# CntrlBoardV2_0.net
KiCad netlist of a schematic drawn in EAGLE
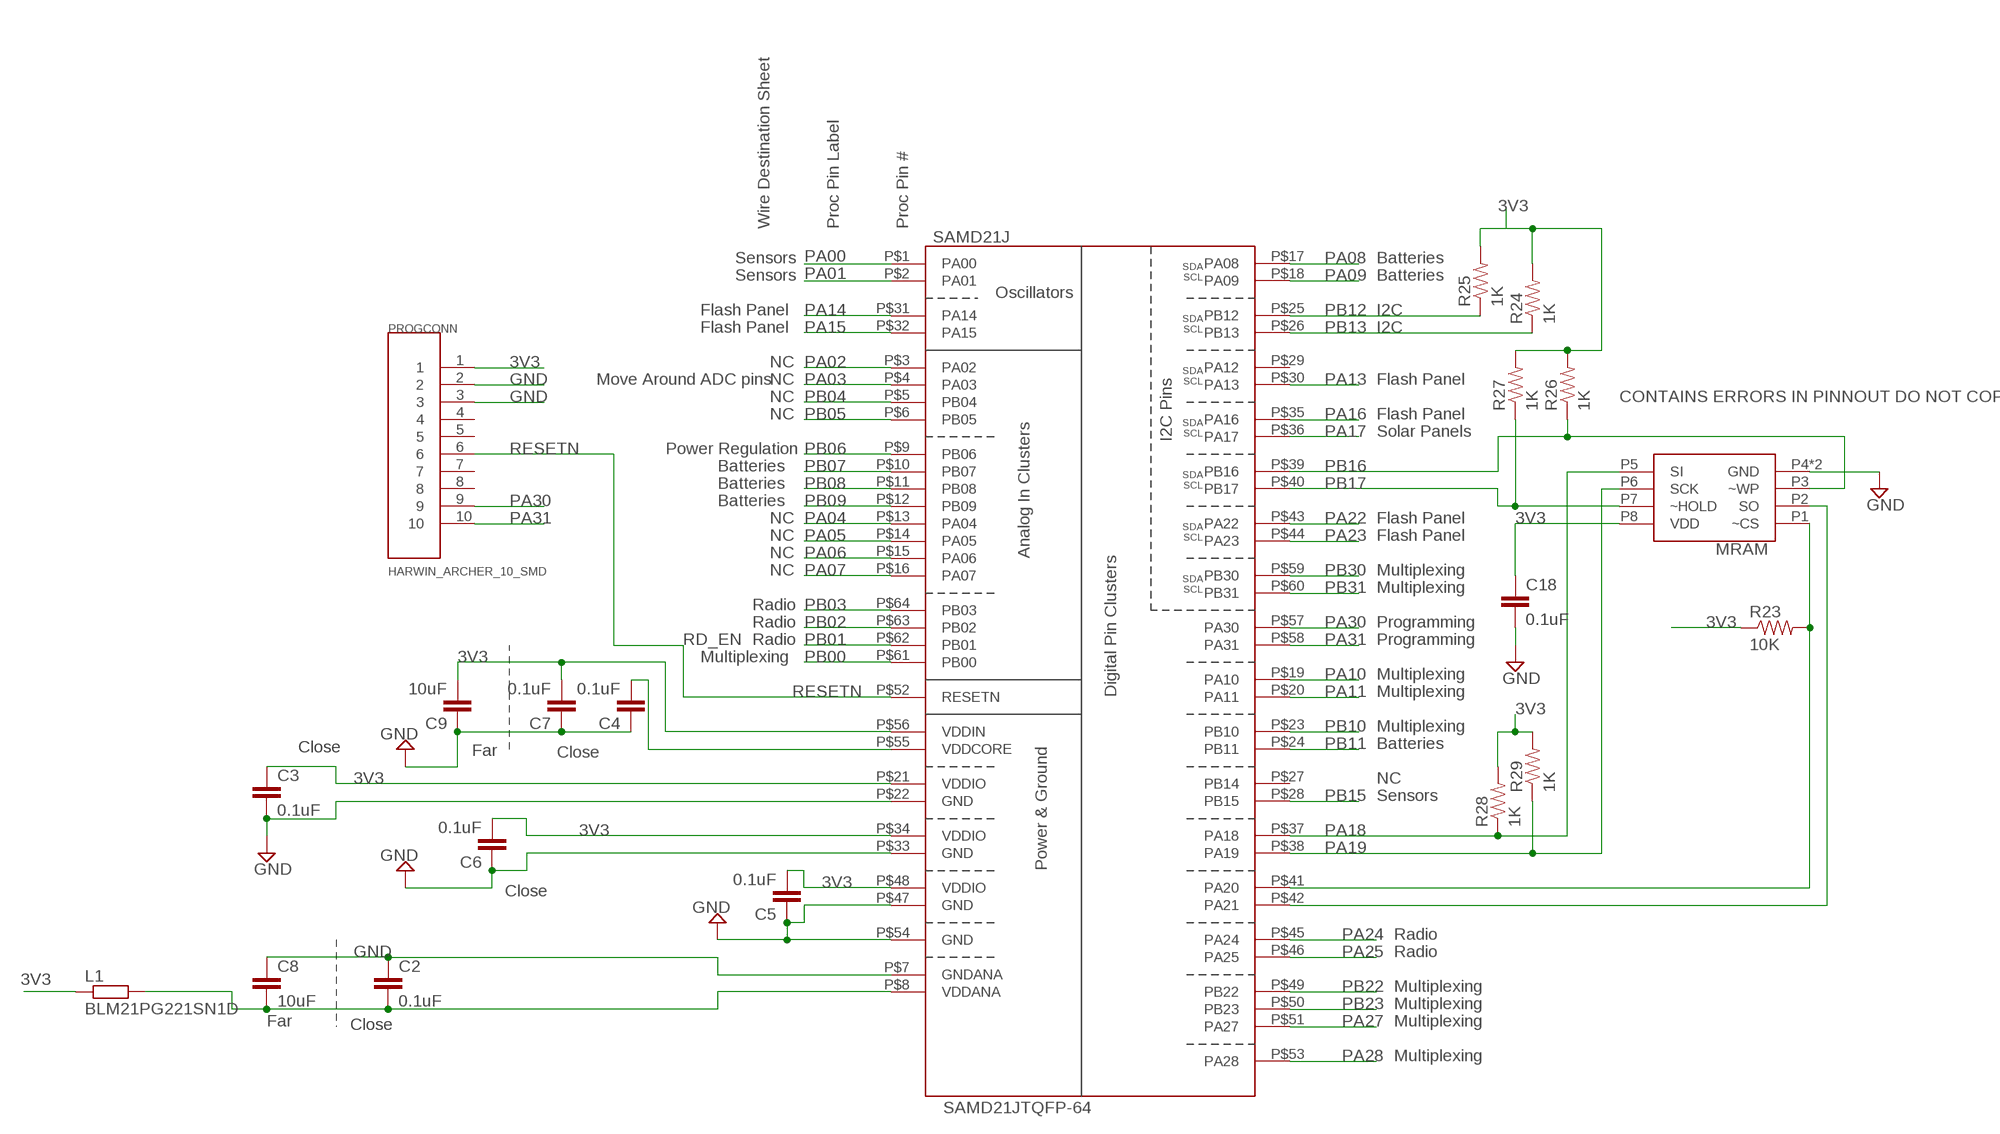
[diagram p0: schematic, sheet 1]
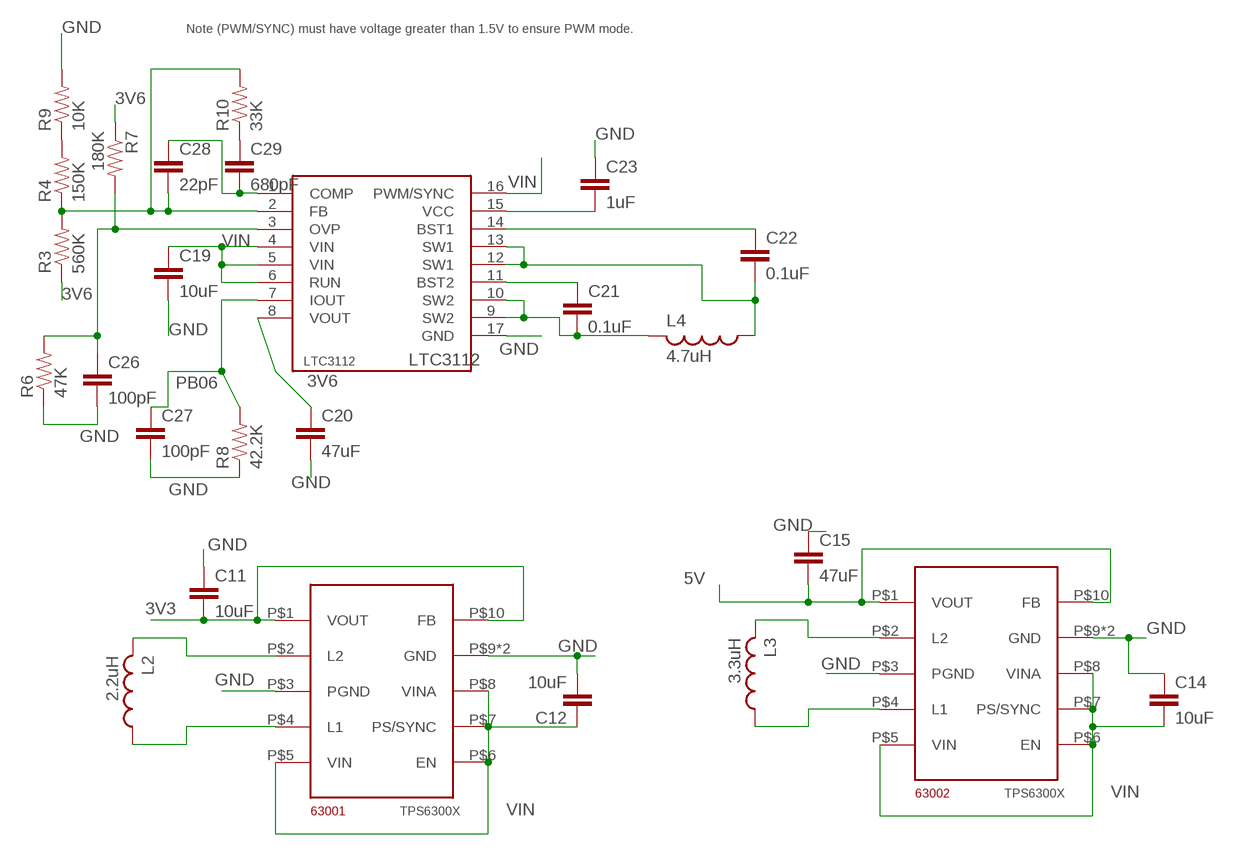
[diagram p1: schematic, sheet 2]
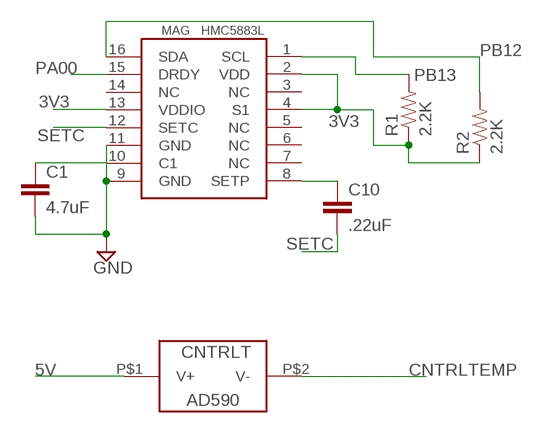
[diagram p2: schematic, sheet 3]
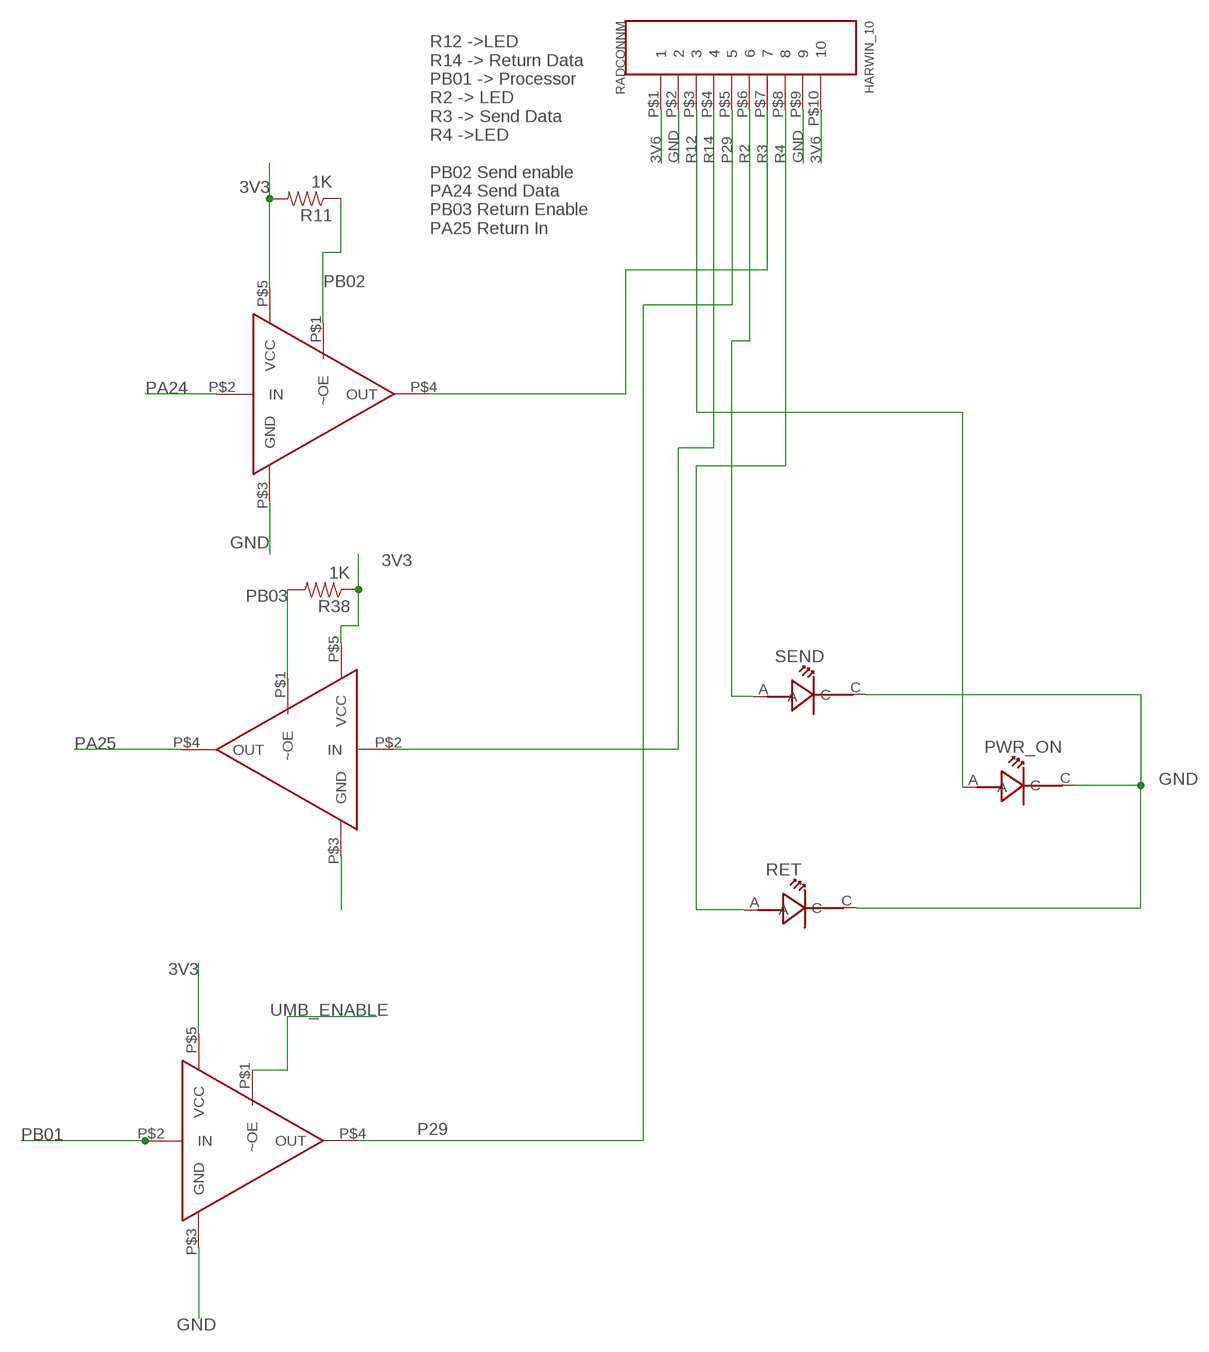
[diagram p3: schematic, sheet 4]
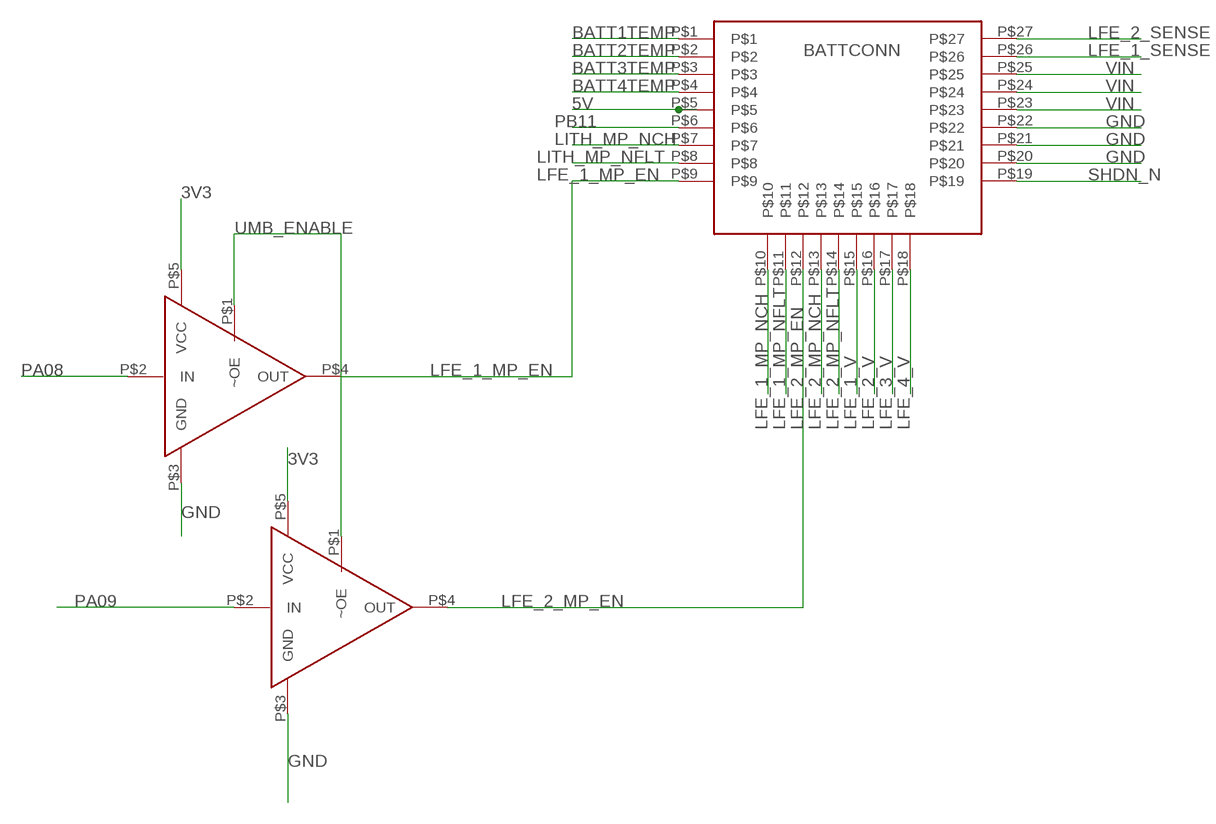
[diagram p4: schematic, sheet 5]
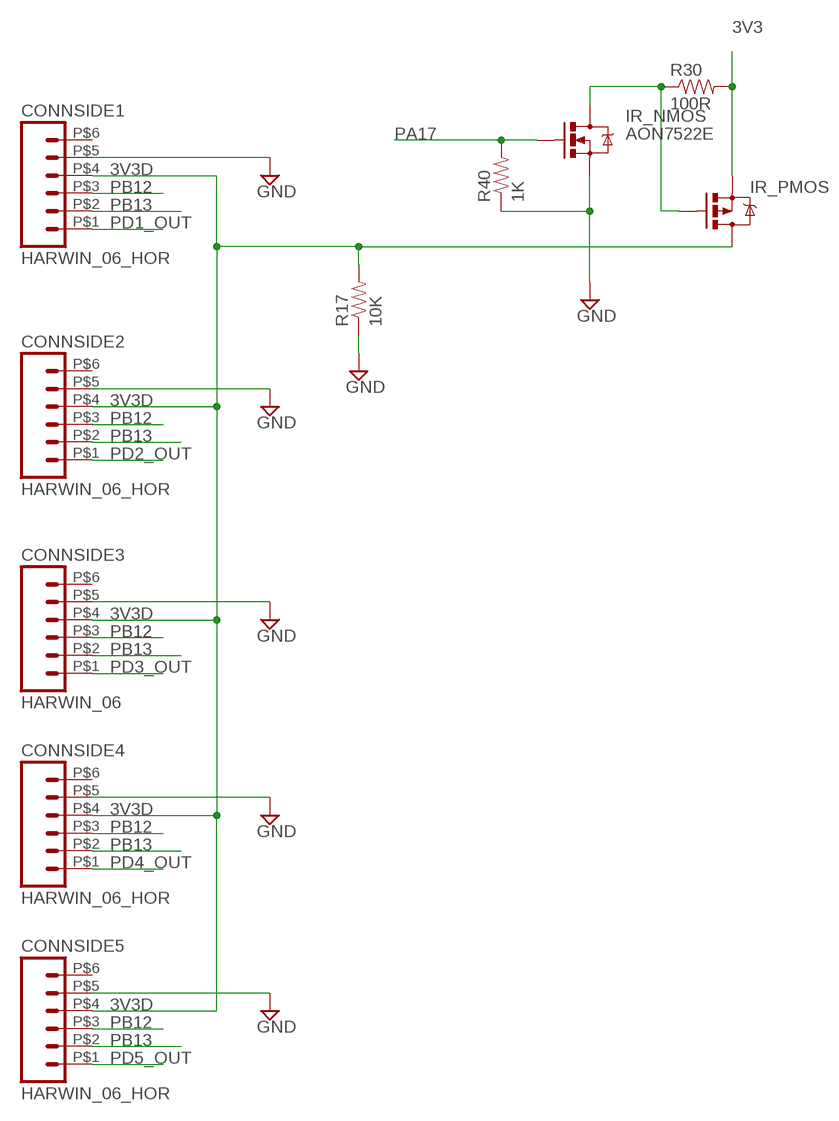
[diagram p5: schematic, sheet 6]
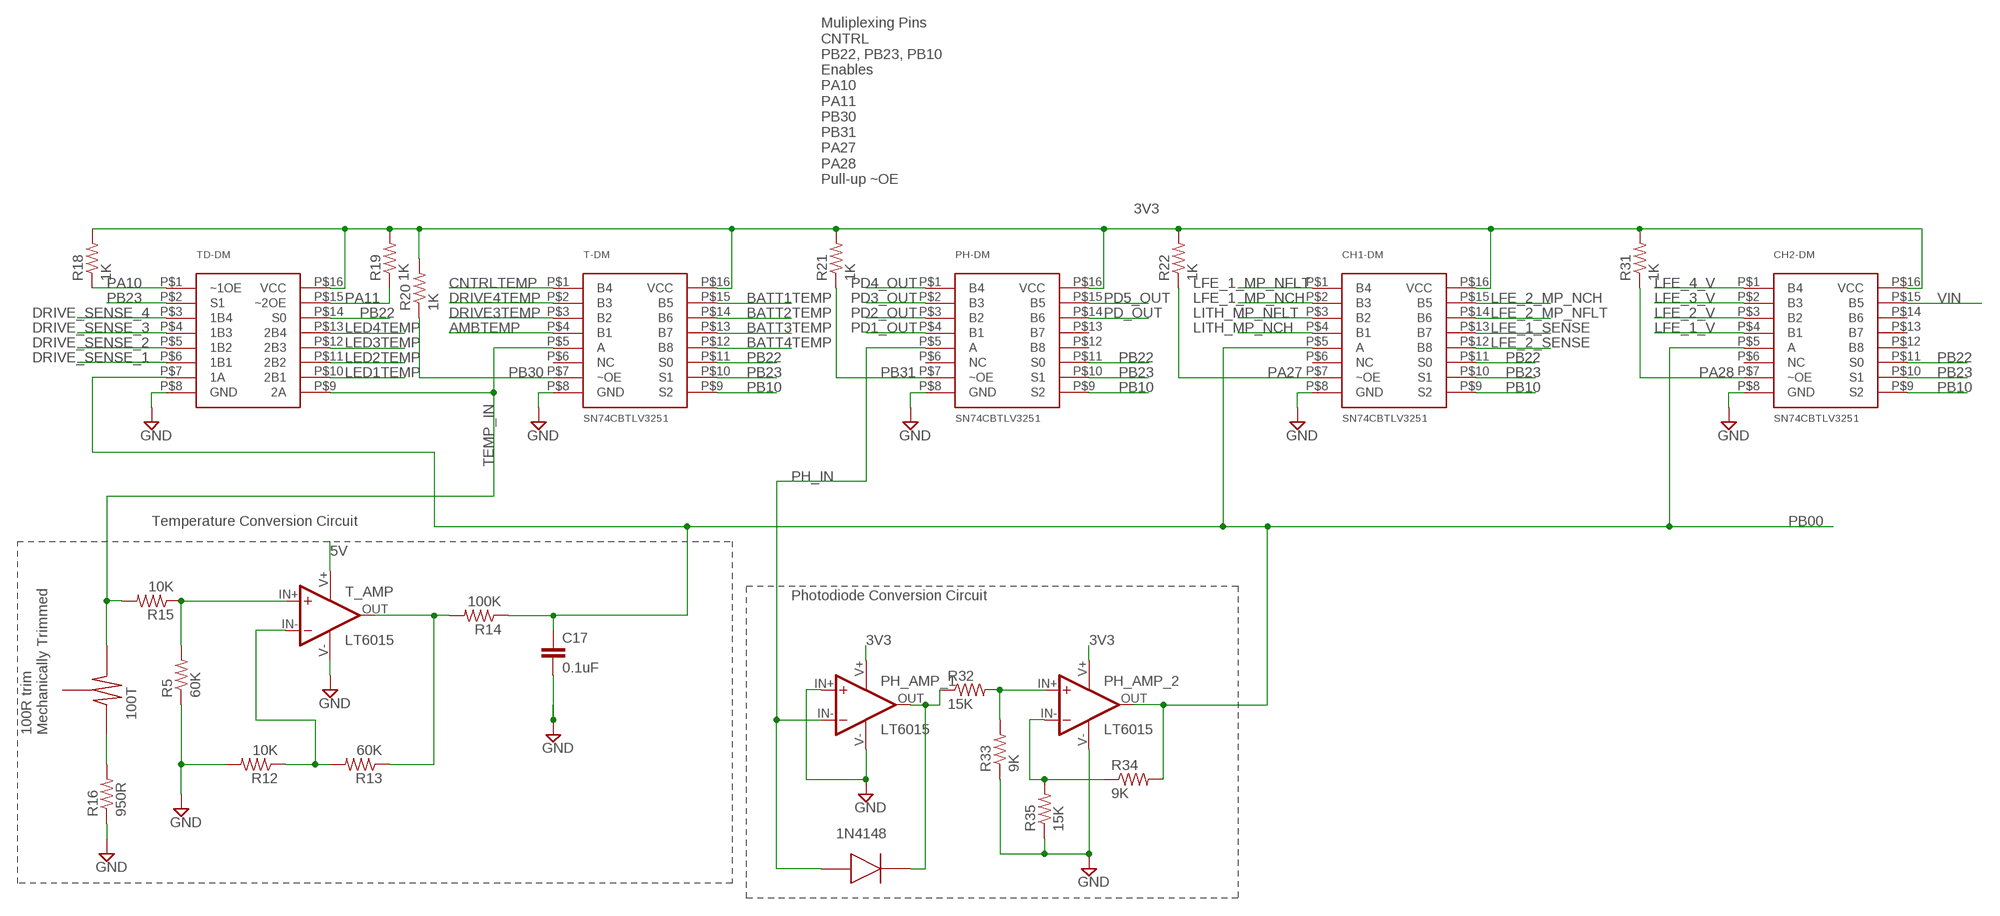
[diagram p6: schematic, sheet 7]
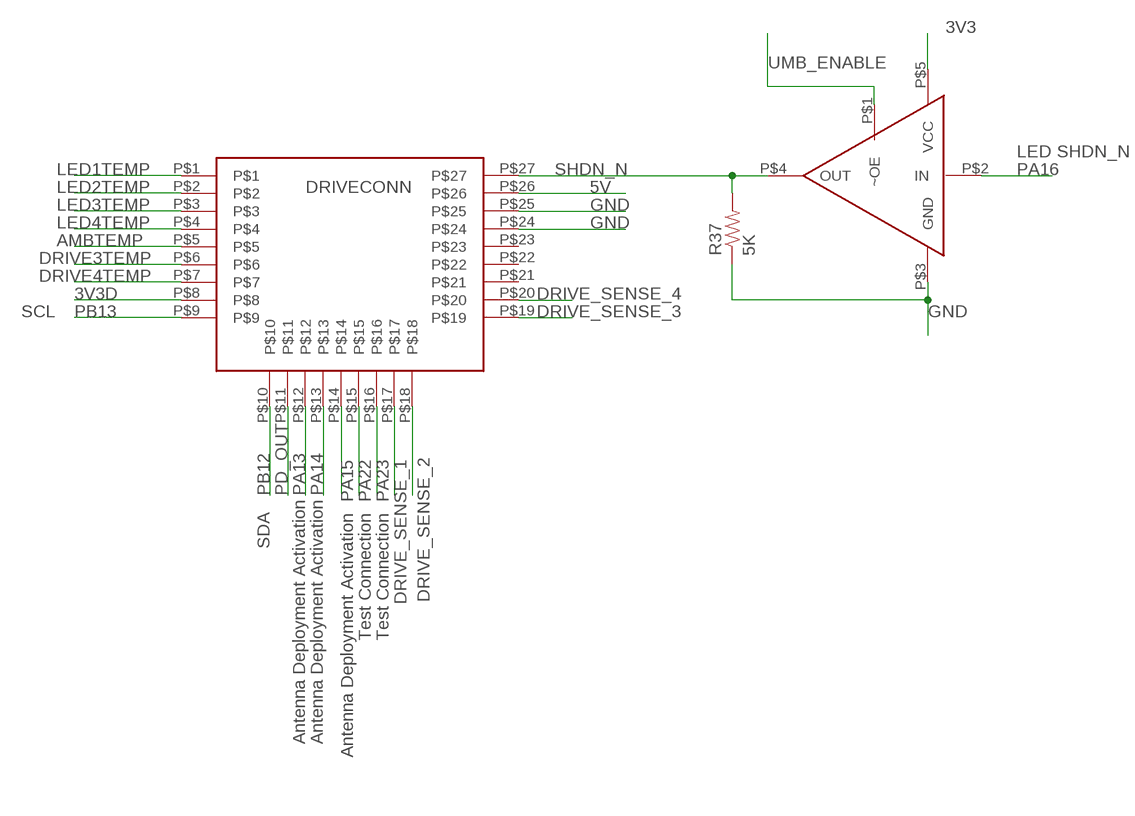
[diagram p7: schematic, sheet 8]
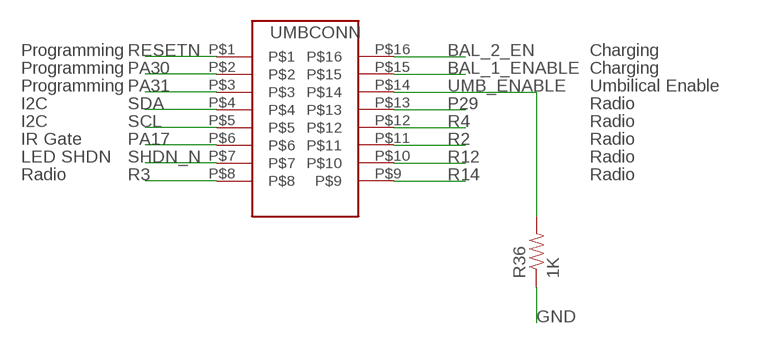
[diagram p8: schematic, sheet 9]

(export (version "E")
  (design (tool "Eeschema 10.0.6"))
  (components
    (comp (ref "R36")
      (value "1K")
      (footprint "eagle-import:0805")
      (libsource (lib "eagle-import") (part "RESISTOR"))
    )
    (comp (ref "UMBCONN")
      (value "HARWIN_16")
      (footprint "eagle-import:HARWIN_DATAMATE_16")
      (libsource (lib "eagle-import") (part "HARWIN_16"))
    )
    (comp (ref "1N4148")
      (value "1N4148WS")
      (footprint "eagle-import:SOD-323F")
      (libsource (lib "eagle-import") (part "1N4148WS"))
    )
    (comp (ref "100T")
      (value "TRIMPOT-TC33")
      (footprint "eagle-import:TC33X-2")
      (libsource (lib "eagle-import") (part "TRIMPOT-TC33"))
    )
    (comp (ref "C17")
      (value "0.1uF")
      (footprint "eagle-import:0805")
      (libsource (lib "eagle-import") (part "CAP0805"))
    )
    (comp (ref "CH1-DM")
      (value "SN74CBTLV3251")
      (footprint "eagle-import:TSSOP-16")
      (libsource (lib "eagle-import") (part "SN74CBTLV3251"))
    )
    (comp (ref "CH2-DM")
      (value "SN74CBTLV3251")
      (footprint "eagle-import:TSSOP-16")
      (libsource (lib "eagle-import") (part "SN74CBTLV3251"))
    )
    (comp (ref "PH-DM")
      (value "SN74CBTLV3251")
      (footprint "eagle-import:TSSOP-16")
      (libsource (lib "eagle-import") (part "SN74CBTLV3251"))
    )
    (comp (ref "PH_AMP_1")
      (value "LT6015")
      (footprint "eagle-import:SOT23-5")
      (libsource (lib "eagle-import") (part "LT6015"))
    )
    (comp (ref "PH_AMP_2")
      (value "LT6015")
      (footprint "eagle-import:SOT23-5")
      (libsource (lib "eagle-import") (part "LT6015"))
    )
    (comp (ref "R5")
      (value "60K")
      (footprint "eagle-import:0805")
      (libsource (lib "eagle-import") (part "RESISTOR"))
    )
    (comp (ref "R12")
      (value "10K")
      (footprint "eagle-import:0805")
      (libsource (lib "eagle-import") (part "RESISTOR"))
    )
    (comp (ref "R13")
      (value "60K")
      (footprint "eagle-import:0805")
      (libsource (lib "eagle-import") (part "RESISTOR"))
    )
    (comp (ref "R14")
      (value "100K")
      (footprint "eagle-import:0805")
      (libsource (lib "eagle-import") (part "RESISTOR"))
    )
    (comp (ref "R15")
      (value "10K")
      (footprint "eagle-import:0805")
      (libsource (lib "eagle-import") (part "RESISTOR"))
    )
    (comp (ref "R16")
      (value "950R")
      (footprint "eagle-import:0805")
      (libsource (lib "eagle-import") (part "RESISTOR"))
    )
    (comp (ref "R18")
      (value "1K")
      (footprint "eagle-import:0805")
      (libsource (lib "eagle-import") (part "RESISTOR"))
    )
    (comp (ref "R19")
      (value "1K")
      (footprint "eagle-import:0805")
      (libsource (lib "eagle-import") (part "RESISTOR"))
    )
    (comp (ref "R20")
      (value "1K")
      (footprint "eagle-import:0805")
      (libsource (lib "eagle-import") (part "RESISTOR"))
    )
    (comp (ref "R21")
      (value "1K")
      (footprint "eagle-import:0805")
      (libsource (lib "eagle-import") (part "RESISTOR"))
    )
    (comp (ref "R22")
      (value "1K")
      (footprint "eagle-import:0805")
      (libsource (lib "eagle-import") (part "RESISTOR"))
    )
    (comp (ref "R31")
      (value "1K")
      (footprint "eagle-import:0805")
      (libsource (lib "eagle-import") (part "RESISTOR"))
    )
    (comp (ref "R32")
      (value "15K")
      (footprint "eagle-import:0805")
      (libsource (lib "eagle-import") (part "RESISTOR"))
    )
    (comp (ref "R33")
      (value "9K")
      (footprint "eagle-import:0805")
      (libsource (lib "eagle-import") (part "RESISTOR"))
    )
    (comp (ref "R34")
      (value "9K")
      (footprint "eagle-import:0805")
      (libsource (lib "eagle-import") (part "RESISTOR"))
    )
    (comp (ref "R35")
      (value "15K")
      (footprint "eagle-import:0805")
      (libsource (lib "eagle-import") (part "RESISTOR"))
    )
    (comp (ref "T-DM")
      (value "SN74CBTLV3251")
      (footprint "eagle-import:TSSOP-16")
      (libsource (lib "eagle-import") (part "SN74CBTLV3251"))
    )
    (comp (ref "TD-DM")
      (value "SN74CBTLV3253")
      (footprint "eagle-import:TSSOP-16")
      (libsource (lib "eagle-import") (part "SN74CBTLV3253"))
    )
    (comp (ref "T_AMP")
      (value "LT6015")
      (footprint "eagle-import:SOT23-5")
      (libsource (lib "eagle-import") (part "LT6015"))
    )
    (comp (ref "C2")
      (value "0.1uF")
      (footprint "eagle-import:0805")
      (fields (field (name "MPN") "0603YC104JAT2A"))
      (libsource (lib "eagle-import") (part "CAP0805"))
    )
    (comp (ref "C3")
      (value "0.1uF")
      (footprint "eagle-import:0805")
      (fields (field (name "MPN") "0603YC104JAT2A"))
      (libsource (lib "eagle-import") (part "CAP0805"))
    )
    (comp (ref "C4")
      (value "0.1uF")
      (footprint "eagle-import:0805")
      (fields (field (name "MPN") "0603YC104JAT2A"))
      (libsource (lib "eagle-import") (part "CAP0805"))
    )
    (comp (ref "C5")
      (value "0.1uF")
      (footprint "eagle-import:0805")
      (fields (field (name "MPN") "0603YC104JAT2A"))
      (libsource (lib "eagle-import") (part "CAP0805"))
    )
    (comp (ref "C6")
      (value "0.1uF")
      (footprint "eagle-import:0805")
      (fields (field (name "MPN") "0603YC104JAT2A"))
      (libsource (lib "eagle-import") (part "CAP0805"))
    )
    (comp (ref "C7")
      (value "0.1uF")
      (footprint "eagle-import:0805")
      (fields (field (name "MPN") "0603YC104JAT2A"))
      (libsource (lib "eagle-import") (part "CAP0805"))
    )
    (comp (ref "C8")
      (value "10uF")
      (footprint "eagle-import:0805")
      (fields (field (name "MF") "AVX CORPORATION") (field (name "MPN") "08056D106KAT2A"))
      (libsource (lib "eagle-import") (part "CAP0805"))
    )
    (comp (ref "C9")
      (value "10uF")
      (footprint "eagle-import:0805")
      (fields (field (name "MF") "AVX CORPORATION") (field (name "MPN") "08056D106KAT2A"))
      (libsource (lib "eagle-import") (part "CAP0805"))
    )
    (comp (ref "C18")
      (value "0.1uF")
      (footprint "eagle-import:0805")
      (fields (field (name "MPN") "0603YC104JAT2A"))
      (libsource (lib "eagle-import") (part "CAP0805"))
    )
    (comp (ref "L1")
      (value "BLM21PG221SN1D")
      (footprint "eagle-import:R0805")
      (libsource (lib "eagle-import") (part "R-EU_R0805"))
    )
    (comp (ref "MRAM")
      (value "MR25H10CDC")
      (footprint "eagle-import:8PXMO-229")
      (libsource (lib "eagle-import") (part "MR25H10CDC"))
    )
    (comp (ref "PROGCONN")
      (value "HARWIN_ARCHER_10_SMD")
      (footprint "eagle-import:HARWIN_ARCHER_10_SMD")
      (libsource (lib "eagle-import") (part "HARWIN_ARCHER_10_SMD"))
    )
    (comp (ref "R23")
      (value "10K")
      (footprint "eagle-import:0805")
      (libsource (lib "eagle-import") (part "RESISTOR"))
    )
    (comp (ref "R24")
      (value "1K")
      (footprint "eagle-import:0805")
      (libsource (lib "eagle-import") (part "RESISTOR"))
    )
    (comp (ref "R25")
      (value "1K")
      (footprint "eagle-import:0805")
      (libsource (lib "eagle-import") (part "RESISTOR"))
    )
    (comp (ref "R26")
      (value "1K")
      (footprint "eagle-import:0805")
      (libsource (lib "eagle-import") (part "RESISTOR"))
    )
    (comp (ref "R27")
      (value "1K")
      (footprint "eagle-import:0805")
      (libsource (lib "eagle-import") (part "RESISTOR"))
    )
    (comp (ref "R28")
      (value "1K")
      (footprint "eagle-import:0805")
      (libsource (lib "eagle-import") (part "RESISTOR"))
    )
    (comp (ref "R29")
      (value "1K")
      (footprint "eagle-import:0805")
      (libsource (lib "eagle-import") (part "RESISTOR"))
    )
    (comp (ref "SAMD21J")
      (value "SAMD21JTQFP-64")
      (footprint "eagle-import:TQFP-64")
      (libsource (lib "eagle-import") (part "SAMD21JTQFP-64"))
    )
    (comp (ref "BAL_1_BUF")
      (value "SN74LVC1G125")
      (footprint "eagle-import:SC70")
      (libsource (lib "eagle-import") (part "SN74LVC1G125"))
    )
    (comp (ref "BAL_2_BUF")
      (value "SN74LVC1G125")
      (footprint "eagle-import:SC70")
      (libsource (lib "eagle-import") (part "SN74LVC1G125"))
    )
    (comp (ref "BATTCONN")
      (value "HARWIN_27")
      (footprint "eagle-import:HARWIN_DATAMATE_27")
      (libsource (lib "eagle-import") (part "HARWIN_27"))
    )
    (comp (ref "DRIVECONN")
      (value "HARWIN_27_HOR")
      (footprint "eagle-import:HARWIN_DATAMATE_27_HOR")
      (libsource (lib "eagle-import") (part "HARWIN_27_HOR"))
    )
    (comp (ref "LED_EN_BUF")
      (value "SN74LVC1G125")
      (footprint "eagle-import:SC70")
      (libsource (lib "eagle-import") (part "SN74LVC1G125"))
    )
    (comp (ref "R37")
      (value "5K")
      (footprint "eagle-import:0805")
      (libsource (lib "eagle-import") (part "RESISTOR"))
    )
    (comp (ref "C1")
      (value "4.7uF")
      (footprint "eagle-import:0805")
      (fields (field (name "MF") "AVX CORPORATION") (field (name "MPN") "08056D475KAT2A"))
      (libsource (lib "eagle-import") (part "CAP0805"))
    )
    (comp (ref "C10")
      (value ".22uF")
      (footprint "eagle-import:0805")
      (fields (field (name "MF") "AVX CORPORATION") (field (name "MPN") "08053C224KAT2A"))
      (libsource (lib "eagle-import") (part "CAP0805"))
    )
    (comp (ref "CNTRLT")
      (value "AD590-TH")
      (footprint "eagle-import:AD590TH")
      (libsource (lib "eagle-import") (part "AD590-TH"))
    )
    (comp (ref "MAG")
      (value "HMC5883L")
      (footprint "eagle-import:HMC5883L")
      (fields (field (name "MPN") "HMC5883L-TR"))
      (libsource (lib "eagle-import") (part "HMC5883L"))
    )
    (comp (ref "R1")
      (value "2.2K")
      (footprint "eagle-import:0805")
      (fields (field (name "MPN") "SR1-0805-222"))
      (libsource (lib "eagle-import") (part "RESISTOR"))
    )
    (comp (ref "R2")
      (value "2.2K")
      (footprint "eagle-import:0805")
      (fields (field (name "MPN") "SR1-0805-222"))
      (libsource (lib "eagle-import") (part "RESISTOR"))
    )
    (comp (ref "PWR_ON")
      (value "LT-T673-Q1R2-25-Z")
      (footprint "eagle-import:PLCC-2")
      (libsource (lib "eagle-import") (part "LT-T673-Q1R2-25-Z"))
    )
    (comp (ref "R11")
      (value "1K")
      (footprint "eagle-import:0805")
      (libsource (lib "eagle-import") (part "RESISTOR"))
    )
    (comp (ref "R38")
      (value "1K")
      (footprint "eagle-import:0805")
      (libsource (lib "eagle-import") (part "RESISTOR"))
    )
    (comp (ref "RADCONNM")
      (value "HARWIN_10")
      (footprint "eagle-import:HARWIN_DATAMATE_10")
      (libsource (lib "eagle-import") (part "HARWIN_10"))
    )
    (comp (ref "RAD_SHDN_BUF")
      (value "SN74LVC1G125")
      (footprint "eagle-import:SC70")
      (libsource (lib "eagle-import") (part "SN74LVC1G125"))
    )
    (comp (ref "RET")
      (value "LT-T673-Q1R2-25-Z")
      (footprint "eagle-import:PLCC-2")
      (libsource (lib "eagle-import") (part "LT-T673-Q1R2-25-Z"))
    )
    (comp (ref "RX_BUF")
      (value "SN74LVC1G125")
      (footprint "eagle-import:SC70")
      (libsource (lib "eagle-import") (part "SN74LVC1G125"))
    )
    (comp (ref "SEND")
      (value "LT-T673-Q1R2-25-Z")
      (footprint "eagle-import:PLCC-2")
      (libsource (lib "eagle-import") (part "LT-T673-Q1R2-25-Z"))
    )
    (comp (ref "TX_BUF")
      (value "SN74LVC1G125")
      (footprint "eagle-import:SC70")
      (libsource (lib "eagle-import") (part "SN74LVC1G125"))
    )
    (comp (ref "CONNSIDE1")
      (value "HARWIN_06_HOR")
      (footprint "eagle-import:HARWIN_DATAMATE_6_HOR")
      (libsource (lib "eagle-import") (part "HARWIN_06_HOR"))
    )
    (comp (ref "CONNSIDE2")
      (value "HARWIN_06_HOR")
      (footprint "eagle-import:HARWIN_DATAMATE_6_HOR")
      (libsource (lib "eagle-import") (part "HARWIN_06_HOR"))
    )
    (comp (ref "CONNSIDE3")
      (value "HARWIN_06")
      (footprint "eagle-import:HARWIN_DATAMATE_6")
      (libsource (lib "eagle-import") (part "HARWIN_06"))
    )
    (comp (ref "CONNSIDE4")
      (value "HARWIN_06_HOR")
      (footprint "eagle-import:HARWIN_DATAMATE_6_HOR")
      (libsource (lib "eagle-import") (part "HARWIN_06_HOR"))
    )
    (comp (ref "CONNSIDE5")
      (value "HARWIN_06_HOR")
      (footprint "eagle-import:HARWIN_DATAMATE_6_HOR")
      (libsource (lib "eagle-import") (part "HARWIN_06_HOR"))
    )
    (comp (ref "IR_NMOS")
      (value "AON7522E")
      (footprint "eagle-import:DFN3")
      (libsource (lib "eagle-import") (part "AON7522E"))
    )
    (comp (ref "IR_PMOS")
      (value "POWERPMOS")
      (footprint "eagle-import:SO08")
      (libsource (lib "eagle-import") (part "POWERPMOS"))
    )
    (comp (ref "R17")
      (value "10K")
      (footprint "eagle-import:0805")
      (libsource (lib "eagle-import") (part "RESISTOR"))
    )
    (comp (ref "R30")
      (value "100R")
      (footprint "eagle-import:0805")
      (libsource (lib "eagle-import") (part "RESISTOR"))
    )
    (comp (ref "R40")
      (value "1K")
      (footprint "eagle-import:0805")
      (libsource (lib "eagle-import") (part "RESISTOR"))
    )
    (comp (ref "63001")
      (value "TPS6300X")
      (footprint "eagle-import:QFN10_POWERPAD")
      (libsource (lib "eagle-import") (part "TPS6300X"))
    )
    (comp (ref "63002")
      (value "TPS6300X")
      (footprint "eagle-import:QFN10_POWERPAD")
      (libsource (lib "eagle-import") (part "TPS6300X"))
    )
    (comp (ref "C11")
      (value "10uF")
      (footprint "eagle-import:0603-CAP")
      (libsource (lib "eagle-import") (part "CAP0603-CAP"))
    )
    (comp (ref "C12")
      (value "10uF")
      (footprint "eagle-import:0603-CAP")
      (libsource (lib "eagle-import") (part "CAP0603-CAP"))
    )
    (comp (ref "C14")
      (value "10uF")
      (footprint "eagle-import:0603-CAP")
      (fields (field (name "MPN") "C1608X5R1A225K080AC"))
      (libsource (lib "eagle-import") (part "CAP0603-CAP"))
    )
    (comp (ref "C15")
      (value "47uF")
      (footprint "eagle-import:0603-CAP")
      (fields (field (name "MPN") "EMK107B7474KA-T"))
      (libsource (lib "eagle-import") (part "CAP0603-CAP"))
    )
    (comp (ref "C19")
      (value "10uF")
      (footprint "eagle-import:0603-CAP")
      (libsource (lib "eagle-import") (part "CAP0603-CAP"))
    )
    (comp (ref "C20")
      (value "47uF")
      (footprint "eagle-import:0805")
      (fields (field (name "MPN") "EMK107B7474KA-T"))
      (libsource (lib "eagle-import") (part "CAP0805"))
    )
    (comp (ref "C21")
      (value "0.1uF")
      (footprint "eagle-import:0603-CAP")
      (fields (field (name "MPN") "0603YC104JAT2A"))
      (libsource (lib "eagle-import") (part "CAP0603-CAP"))
    )
    (comp (ref "C22")
      (value "0.1uF")
      (footprint "eagle-import:0603-CAP")
      (fields (field (name "MPN") "0603YC104JAT2A"))
      (libsource (lib "eagle-import") (part "CAP0603-CAP"))
    )
    (comp (ref "C23")
      (value "1uF")
      (footprint "eagle-import:0603-CAP")
      (libsource (lib "eagle-import") (part "CAP0603-CAP"))
    )
    (comp (ref "C26")
      (value "100pF")
      (footprint "eagle-import:0805")
      (fields (field (name "MF") "AVX CORPORATION") (field (name "MPN") "08051A101J4T4A"))
      (libsource (lib "eagle-import") (part "CAP0805"))
    )
    (comp (ref "C27")
      (value "100pF")
      (footprint "eagle-import:0805")
      (fields (field (name "MF") "AVX CORPORATION") (field (name "MPN") "08051A101J4T4A"))
      (libsource (lib "eagle-import") (part "CAP0805"))
    )
    (comp (ref "C28")
      (value "22pF")
      (footprint "eagle-import:0805")
      (fields (field (name "MF") "AVX CORPORATION") (field (name "MPN") "08051A220JAT2A"))
      (libsource (lib "eagle-import") (part "CAP0805"))
    )
    (comp (ref "C29")
      (value "680pF")
      (footprint "eagle-import:0805")
      (fields (field (name "MPN") "08055C681KAT2A"))
      (libsource (lib "eagle-import") (part "CAP0805"))
    )
    (comp (ref "L2")
      (value "2.2uH")
      (footprint "eagle-import:L3225M")
      (libsource (lib "eagle-import") (part "L-USL3225M"))
    )
    (comp (ref "L3")
      (value "3.3uH")
      (footprint "eagle-import:L3225M")
      (fields (field (name "MPN") "JMK212BJ335KG-T"))
      (libsource (lib "eagle-import") (part "L-USL3225M"))
    )
    (comp (ref "L4")
      (value "4.7uH")
      (footprint "eagle-import:L3225M")
      (libsource (lib "eagle-import") (part "L-USL3225M"))
    )
    (comp (ref "LTC3112")
      (value "LTC3112")
      (footprint "eagle-import:DHD16")
      (fields (field (name "MPN") "LTC3112EFE#PBF"))
      (libsource (lib "eagle-import") (part "LTC3112"))
    )
    (comp (ref "R3")
      (value "560K")
      (footprint "eagle-import:0805")
      (fields (field (name "MPN") "MC01W08051560K"))
      (libsource (lib "eagle-import") (part "RESISTOR"))
    )
    (comp (ref "R4")
      (value "150K")
      (footprint "eagle-import:0805")
      (libsource (lib "eagle-import") (part "RESISTOR"))
    )
    (comp (ref "R6")
      (value "47K")
      (footprint "eagle-import:0805")
      (libsource (lib "eagle-import") (part "RESISTOR"))
    )
    (comp (ref "R7")
      (value "180K")
      (footprint "eagle-import:0805")
      (fields (field (name "MPN") "ERJ-6GEYJ184V"))
      (libsource (lib "eagle-import") (part "RESISTOR"))
    )
    (comp (ref "R8")
      (value "42.2K")
      (footprint "eagle-import:0805")
      (libsource (lib "eagle-import") (part "RESISTOR"))
    )
    (comp (ref "R9")
      (value "10K")
      (footprint "eagle-import:0805")
      (libsource (lib "eagle-import") (part "RESISTOR"))
    )
    (comp (ref "R10")
      (value "33K")
      (footprint "eagle-import:0805")
      (libsource (lib "eagle-import") (part "RESISTOR"))
    )
  )
  (nets
    (net (code "1") (name "3V3") (class "Default")
      (node (ref "63001") (pin "P$1") (pinfunction "VOUT_P$1") (pintype "output"))
      (node (ref "63001") (pin "P$10") (pinfunction "FB_P$10") (pintype "input"))
      (node (ref "BAL_1_BUF") (pin "P$5") (pinfunction "VCC_P$5") (pintype "bidirectional"))
      (node (ref "BAL_2_BUF") (pin "P$5") (pinfunction "VCC_P$5") (pintype "bidirectional"))
      (node (ref "C11") (pin "2") (pinfunction "2_2") (pintype "passive"))
      (node (ref "C18") (pin "1") (pinfunction "1_1") (pintype "passive"))
      (node (ref "C3") (pin "1") (pinfunction "1_1") (pintype "passive"))
      (node (ref "C5") (pin "2") (pinfunction "2_2") (pintype "passive"))
      (node (ref "C6") (pin "2") (pinfunction "2_2") (pintype "passive"))
      (node (ref "C7") (pin "2") (pinfunction "2_2") (pintype "passive"))
      (node (ref "C9") (pin "2") (pinfunction "2_2") (pintype "passive"))
      (node (ref "CH1-DM") (pin "P$16") (pinfunction "VCC_P$16") (pintype "bidirectional"))
      (node (ref "CH2-DM") (pin "P$16") (pinfunction "VCC_P$16") (pintype "bidirectional"))
      (node (ref "IR_PMOS") (pin "1") (pinfunction "S_1") (pintype "passive"))
      (node (ref "IR_PMOS") (pin "2") (pinfunction "S_2") (pintype "passive"))
      (node (ref "IR_PMOS") (pin "3") (pinfunction "S_3") (pintype "passive"))
      (node (ref "L1") (pin "1") (pinfunction "1_1") (pintype "passive"))
      (node (ref "LED_EN_BUF") (pin "P$5") (pinfunction "VCC_P$5") (pintype "bidirectional"))
      (node (ref "MAG") (pin "13") (pinfunction "VDDIO_13") (pintype "bidirectional"))
      (node (ref "MAG") (pin "2") (pinfunction "VDD_2") (pintype "bidirectional"))
      (node (ref "MAG") (pin "4") (pinfunction "S1_4") (pintype "bidirectional"))
      (node (ref "MRAM") (pin "P8") (pinfunction "VDD_P8") (pintype "bidirectional"))
      (node (ref "PH-DM") (pin "P$16") (pinfunction "VCC_P$16") (pintype "bidirectional"))
      (node (ref "PH_AMP_1") (pin "V+") (pinfunction "V+_V+") (pintype "power_in"))
      (node (ref "PH_AMP_2") (pin "V+") (pinfunction "V+_V+") (pintype "power_in"))
      (node (ref "PROGCONN") (pin "1") (pinfunction "1_1") (pintype "bidirectional"))
      (node (ref "R1") (pin "1") (pinfunction "1_1") (pintype "passive"))
      (node (ref "R11") (pin "2") (pinfunction "2_2") (pintype "passive"))
      (node (ref "R18") (pin "2") (pinfunction "2_2") (pintype "passive"))
      (node (ref "R19") (pin "2") (pinfunction "2_2") (pintype "passive"))
      (node (ref "R2") (pin "1") (pinfunction "1_1") (pintype "passive"))
      (node (ref "R20") (pin "2") (pinfunction "2_2") (pintype "passive"))
      (node (ref "R21") (pin "2") (pinfunction "2_2") (pintype "passive"))
      (node (ref "R22") (pin "2") (pinfunction "2_2") (pintype "passive"))
      (node (ref "R23") (pin "1") (pinfunction "1_1") (pintype "passive"))
      (node (ref "R24") (pin "2") (pinfunction "2_2") (pintype "passive"))
      (node (ref "R25") (pin "2") (pinfunction "2_2") (pintype "passive"))
      (node (ref "R26") (pin "2") (pinfunction "2_2") (pintype "passive"))
      (node (ref "R27") (pin "2") (pinfunction "2_2") (pintype "passive"))
      (node (ref "R28") (pin "2") (pinfunction "2_2") (pintype "passive"))
      (node (ref "R29") (pin "2") (pinfunction "2_2") (pintype "passive"))
      (node (ref "R30") (pin "2") (pinfunction "2_2") (pintype "passive"))
      (node (ref "R31") (pin "2") (pinfunction "2_2") (pintype "passive"))
      (node (ref "R38") (pin "1") (pinfunction "1_1") (pintype "passive"))
      (node (ref "RAD_SHDN_BUF") (pin "P$5") (pinfunction "VCC_P$5") (pintype "bidirectional"))
      (node (ref "RX_BUF") (pin "P$5") (pinfunction "VCC_P$5") (pintype "bidirectional"))
      (node (ref "SAMD21J") (pin "P$21") (pinfunction "VDDIO_P$21") (pintype "power_in"))
      (node (ref "SAMD21J") (pin "P$34") (pinfunction "VDDIO_P$34") (pintype "power_in"))
      (node (ref "SAMD21J") (pin "P$48") (pinfunction "VDDIO_P$48") (pintype "power_in"))
      (node (ref "SAMD21J") (pin "P$56") (pinfunction "VDDIN_P$56") (pintype "power_in"))
      (node (ref "T-DM") (pin "P$16") (pinfunction "VCC_P$16") (pintype "bidirectional"))
      (node (ref "TD-DM") (pin "P$16") (pinfunction "VCC_P$16") (pintype "bidirectional"))
      (node (ref "TX_BUF") (pin "P$5") (pinfunction "VCC_P$5") (pintype "bidirectional"))
    )
    (net (code "2") (name "3V3D") (class "Default")
      (node (ref "CONNSIDE1") (pin "P$4") (pinfunction "4_P$4") (pintype "passive"))
      (node (ref "CONNSIDE2") (pin "P$4") (pinfunction "4_P$4") (pintype "passive"))
      (node (ref "CONNSIDE3") (pin "P$4") (pinfunction "4_P$4") (pintype "passive"))
      (node (ref "CONNSIDE4") (pin "P$4") (pinfunction "4_P$4") (pintype "passive"))
      (node (ref "CONNSIDE5") (pin "P$4") (pinfunction "4_P$4") (pintype "passive"))
      (node (ref "DRIVECONN") (pin "P$8") (pinfunction "P$8_P$8") (pintype "bidirectional"))
      (node (ref "IR_PMOS") (pin "5") (pinfunction "D_5") (pintype "passive"))
      (node (ref "IR_PMOS") (pin "6") (pinfunction "D_6") (pintype "passive"))
      (node (ref "IR_PMOS") (pin "7") (pinfunction "D_7") (pintype "passive"))
      (node (ref "IR_PMOS") (pin "8") (pinfunction "D_8") (pintype "passive"))
      (node (ref "R17") (pin "2") (pinfunction "2_2") (pintype "passive"))
    )
    (net (code "3") (name "3V6") (class "Default")
      (node (ref "C20") (pin "1") (pinfunction "1_1") (pintype "passive"))
      (node (ref "LTC3112") (pin "8") (pinfunction "VOUT_8") (pintype "bidirectional"))
      (node (ref "R3") (pin "1") (pinfunction "1_1") (pintype "passive"))
      (node (ref "R7") (pin "1") (pinfunction "1_1") (pintype "passive"))
      (node (ref "RADCONNM") (pin "P$1") (pinfunction "1_P$1") (pintype "bidirectional"))
      (node (ref "RADCONNM") (pin "P$10") (pinfunction "10_P$10") (pintype "bidirectional"))
    )
    (net (code "4") (name "5V") (class "Default")
      (node (ref "63002") (pin "P$1") (pinfunction "VOUT_P$1") (pintype "output"))
      (node (ref "63002") (pin "P$10") (pinfunction "FB_P$10") (pintype "input"))
      (node (ref "BATTCONN") (pin "P$5") (pinfunction "P$5_P$5") (pintype "bidirectional"))
      (node (ref "C15") (pin "2") (pinfunction "2_2") (pintype "passive"))
      (node (ref "CNTRLT") (pin "P$1") (pinfunction "V+_P$1") (pintype "bidirectional"))
      (node (ref "DRIVECONN") (pin "P$26") (pinfunction "P$26_P$26") (pintype "bidirectional"))
      (node (ref "T_AMP") (pin "V+") (pinfunction "V+_V+") (pintype "power_in"))
    )
    (net (code "5") (name "AMBTEMP") (class "Default")
      (node (ref "DRIVECONN") (pin "P$5") (pinfunction "P$5_P$5") (pintype "bidirectional"))
      (node (ref "T-DM") (pin "P$4") (pinfunction "B1_P$4") (pintype "bidirectional"))
    )
    (net (code "6") (name "BAL_1_ENABLE") (class "Default")
      (node (ref "UMBCONN") (pin "P$15") (pinfunction "P$15_P$15") (pintype "bidirectional"))
    )
    (net (code "7") (name "BAL_2_EN") (class "Default")
      (node (ref "UMBCONN") (pin "P$16") (pinfunction "P$16_P$16") (pintype "bidirectional"))
    )
    (net (code "8") (name "BATT1TEMP") (class "Default")
      (node (ref "BATTCONN") (pin "P$1") (pinfunction "P$1_P$1") (pintype "bidirectional"))
      (node (ref "T-DM") (pin "P$15") (pinfunction "B5_P$15") (pintype "bidirectional"))
    )
    (net (code "9") (name "BATT2TEMP") (class "Default")
      (node (ref "BATTCONN") (pin "P$2") (pinfunction "P$2_P$2") (pintype "bidirectional"))
      (node (ref "T-DM") (pin "P$14") (pinfunction "B6_P$14") (pintype "bidirectional"))
    )
    (net (code "10") (name "BATT3TEMP") (class "Default")
      (node (ref "BATTCONN") (pin "P$3") (pinfunction "P$3_P$3") (pintype "bidirectional"))
      (node (ref "T-DM") (pin "P$13") (pinfunction "B7_P$13") (pintype "bidirectional"))
    )
    (net (code "11") (name "BATT4TEMP") (class "Default")
      (node (ref "BATTCONN") (pin "P$4") (pinfunction "P$4_P$4") (pintype "bidirectional"))
      (node (ref "T-DM") (pin "P$12") (pinfunction "B8_P$12") (pintype "bidirectional"))
    )
    (net (code "12") (name "CNTRLTEMP") (class "Default")
      (node (ref "CNTRLT") (pin "P$2") (pinfunction "V-_P$2") (pintype "bidirectional"))
      (node (ref "T-DM") (pin "P$1") (pinfunction "B4_P$1") (pintype "bidirectional"))
    )
    (net (code "13") (name "DRIVE3TEMP") (class "Default")
      (node (ref "DRIVECONN") (pin "P$6") (pinfunction "P$6_P$6") (pintype "bidirectional"))
      (node (ref "T-DM") (pin "P$3") (pinfunction "B2_P$3") (pintype "bidirectional"))
    )
    (net (code "14") (name "DRIVE4TEMP") (class "Default")
      (node (ref "DRIVECONN") (pin "P$7") (pinfunction "P$7_P$7") (pintype "bidirectional"))
      (node (ref "T-DM") (pin "P$2") (pinfunction "B3_P$2") (pintype "bidirectional"))
    )
    (net (code "15") (name "DRIVE_SENSE_1") (class "Default")
      (node (ref "DRIVECONN") (pin "P$17") (pinfunction "P$17_P$17") (pintype "bidirectional"))
      (node (ref "TD-DM") (pin "P$6") (pinfunction "1B1_P$6") (pintype "bidirectional"))
    )
    (net (code "16") (name "DRIVE_SENSE_2") (class "Default")
      (node (ref "DRIVECONN") (pin "P$18") (pinfunction "P$18_P$18") (pintype "bidirectional"))
      (node (ref "TD-DM") (pin "P$5") (pinfunction "1B2_P$5") (pintype "bidirectional"))
    )
    (net (code "17") (name "DRIVE_SENSE_3") (class "Default")
      (node (ref "DRIVECONN") (pin "P$19") (pinfunction "P$19_P$19") (pintype "bidirectional"))
      (node (ref "TD-DM") (pin "P$4") (pinfunction "1B3_P$4") (pintype "bidirectional"))
    )
    (net (code "18") (name "DRIVE_SENSE_4") (class "Default")
      (node (ref "DRIVECONN") (pin "P$20") (pinfunction "P$20_P$20") (pintype "bidirectional"))
      (node (ref "TD-DM") (pin "P$3") (pinfunction "1B4_P$3") (pintype "bidirectional"))
    )
    (net (code "19") (name "GND") (class "Default")
      (node (ref "63001") (pin "P$3") (pinfunction "PGND_P$3") (pintype "input"))
      (node (ref "63001") (pin "P$9") (pinfunction "GND_P$9") (pintype "input"))
      (node (ref "63001") (pin "PAD") (pinfunction "GND_PAD") (pintype "input"))
      (node (ref "63002") (pin "P$3") (pinfunction "PGND_P$3") (pintype "input"))
      (node (ref "63002") (pin "P$9") (pinfunction "GND_P$9") (pintype "input"))
      (node (ref "63002") (pin "PAD") (pinfunction "GND_PAD") (pintype "input"))
      (node (ref "BAL_1_BUF") (pin "P$3") (pinfunction "GND_P$3") (pintype "bidirectional"))
      (node (ref "BAL_2_BUF") (pin "P$3") (pinfunction "GND_P$3") (pintype "bidirectional"))
      (node (ref "BATTCONN") (pin "P$20") (pinfunction "P$20_P$20") (pintype "bidirectional"))
      (node (ref "BATTCONN") (pin "P$21") (pinfunction "P$21_P$21") (pintype "bidirectional"))
      (node (ref "BATTCONN") (pin "P$22") (pinfunction "P$22_P$22") (pintype "bidirectional"))
      (node (ref "C1") (pin "2") (pinfunction "2_2") (pintype "passive"))
      (node (ref "C11") (pin "1") (pinfunction "1_1") (pintype "passive"))
      (node (ref "C12") (pin "2") (pinfunction "2_2") (pintype "passive"))
      (node (ref "C14") (pin "1") (pinfunction "1_1") (pintype "passive"))
      (node (ref "C15") (pin "1") (pinfunction "1_1") (pintype "passive"))
      (node (ref "C17") (pin "2") (pinfunction "2_2") (pintype "passive"))
      (node (ref "C18") (pin "2") (pinfunction "2_2") (pintype "passive"))
      (node (ref "C19") (pin "2") (pinfunction "2_2") (pintype "passive"))
      (node (ref "C2") (pin "1") (pinfunction "1_1") (pintype "passive"))
      (node (ref "C20") (pin "2") (pinfunction "2_2") (pintype "passive"))
      (node (ref "C23") (pin "1") (pinfunction "1_1") (pintype "passive"))
      (node (ref "C26") (pin "2") (pinfunction "2_2") (pintype "passive"))
      (node (ref "C27") (pin "2") (pinfunction "2_2") (pintype "passive"))
      (node (ref "C3") (pin "2") (pinfunction "2_2") (pintype "passive"))
      (node (ref "C4") (pin "1") (pinfunction "1_1") (pintype "passive"))
      (node (ref "C5") (pin "1") (pinfunction "1_1") (pintype "passive"))
      (node (ref "C6") (pin "1") (pinfunction "1_1") (pintype "passive"))
      (node (ref "C7") (pin "1") (pinfunction "1_1") (pintype "passive"))
      (node (ref "C8") (pin "1") (pinfunction "1_1") (pintype "passive"))
      (node (ref "C9") (pin "1") (pinfunction "1_1") (pintype "passive"))
      (node (ref "CH1-DM") (pin "P$8") (pinfunction "GND_P$8") (pintype "bidirectional"))
      (node (ref "CH2-DM") (pin "P$8") (pinfunction "GND_P$8") (pintype "bidirectional"))
      (node (ref "CONNSIDE1") (pin "P$5") (pinfunction "5_P$5") (pintype "passive"))
      (node (ref "CONNSIDE2") (pin "P$5") (pinfunction "5_P$5") (pintype "passive"))
      (node (ref "CONNSIDE3") (pin "P$5") (pinfunction "5_P$5") (pintype "passive"))
      (node (ref "CONNSIDE4") (pin "P$5") (pinfunction "5_P$5") (pintype "passive"))
      (node (ref "CONNSIDE5") (pin "P$5") (pinfunction "5_P$5") (pintype "passive"))
      (node (ref "DRIVECONN") (pin "P$24") (pinfunction "P$24_P$24") (pintype "bidirectional"))
      (node (ref "DRIVECONN") (pin "P$25") (pinfunction "P$25_P$25") (pintype "bidirectional"))
      (node (ref "IR_NMOS") (pin "P$1") (pinfunction "S_P$1") (pintype "passive"))
      (node (ref "IR_NMOS") (pin "P$2") (pinfunction "S_P$2") (pintype "passive"))
      (node (ref "IR_NMOS") (pin "P$3") (pinfunction "S_P$3") (pintype "passive"))
      (node (ref "LED_EN_BUF") (pin "P$3") (pinfunction "GND_P$3") (pintype "bidirectional"))
      (node (ref "LTC3112") (pin "17") (pinfunction "GND_17") (pintype "bidirectional"))
      (node (ref "MAG") (pin "11") (pinfunction "GND_11") (pintype "bidirectional"))
      (node (ref "MAG") (pin "9") (pinfunction "GND_9") (pintype "bidirectional"))
      (node (ref "MRAM") (pin "P4") (pinfunction "GND_P4") (pintype "bidirectional"))
      (node (ref "MRAM") (pin "P9") (pinfunction "GND_P9") (pintype "bidirectional"))
      (node (ref "PH-DM") (pin "P$8") (pinfunction "GND_P$8") (pintype "bidirectional"))
      (node (ref "PH_AMP_1") (pin "IN+") (pinfunction "IN+_IN+") (pintype "input"))
      (node (ref "PH_AMP_1") (pin "V-") (pinfunction "V-_V-") (pintype "power_in"))
      (node (ref "PH_AMP_2") (pin "V-") (pinfunction "V-_V-") (pintype "power_in"))
      (node (ref "PROGCONN") (pin "2") (pinfunction "2_2") (pintype "bidirectional"))
      (node (ref "PROGCONN") (pin "3") (pinfunction "3_3") (pintype "bidirectional"))
      (node (ref "PWR_ON") (pin "C") (pinfunction "C_C") (pintype "bidirectional"))
      (node (ref "R12") (pin "2") (pinfunction "2_2") (pintype "passive"))
      (node (ref "R16") (pin "1") (pinfunction "1_1") (pintype "passive"))
      (node (ref "R17") (pin "1") (pinfunction "1_1") (pintype "passive"))
      (node (ref "R33") (pin "1") (pinfunction "1_1") (pintype "passive"))
      (node (ref "R35") (pin "1") (pinfunction "1_1") (pintype "passive"))
      (node (ref "R36") (pin "1") (pinfunction "1_1") (pintype "passive"))
      (node (ref "R37") (pin "1") (pinfunction "1_1") (pintype "passive"))
      (node (ref "R40") (pin "1") (pinfunction "1_1") (pintype "passive"))
      (node (ref "R5") (pin "1") (pinfunction "1_1") (pintype "passive"))
      (node (ref "R6") (pin "1") (pinfunction "1_1") (pintype "passive"))
      (node (ref "R8") (pin "1") (pinfunction "1_1") (pintype "passive"))
      (node (ref "R9") (pin "2") (pinfunction "2_2") (pintype "passive"))
      (node (ref "RADCONNM") (pin "P$2") (pinfunction "2_P$2") (pintype "bidirectional"))
      (node (ref "RADCONNM") (pin "P$9") (pinfunction "9_P$9") (pintype "bidirectional"))
      (node (ref "RAD_SHDN_BUF") (pin "P$3") (pinfunction "GND_P$3") (pintype "bidirectional"))
      (node (ref "RET") (pin "C") (pinfunction "C_C") (pintype "bidirectional"))
      (node (ref "RX_BUF") (pin "P$3") (pinfunction "GND_P$3") (pintype "bidirectional"))
      (node (ref "SAMD21J") (pin "P$22") (pinfunction "GND_P$22") (pintype "power_in"))
      (node (ref "SAMD21J") (pin "P$33") (pinfunction "GND_P$33") (pintype "power_in"))
      (node (ref "SAMD21J") (pin "P$47") (pinfunction "GND_P$47") (pintype "power_in"))
      (node (ref "SAMD21J") (pin "P$54") (pinfunction "GND_P$54") (pintype "power_in"))
      (node (ref "SAMD21J") (pin "P$7") (pinfunction "GNDANA_P$7") (pintype "power_in"))
      (node (ref "SEND") (pin "C") (pinfunction "C_C") (pintype "bidirectional"))
      (node (ref "T-DM") (pin "P$8") (pinfunction "GND_P$8") (pintype "bidirectional"))
      (node (ref "TD-DM") (pin "P$8") (pinfunction "GND_P$8") (pintype "bidirectional"))
      (node (ref "TX_BUF") (pin "P$3") (pinfunction "GND_P$3") (pintype "bidirectional"))
      (node (ref "T_AMP") (pin "V-") (pinfunction "V-_V-") (pintype "power_in"))
    )
    (net (code "20") (name "LED1TEMP") (class "Default")
      (node (ref "DRIVECONN") (pin "P$1") (pinfunction "P$1_P$1") (pintype "bidirectional"))
      (node (ref "TD-DM") (pin "P$10") (pinfunction "2B1_P$10") (pintype "bidirectional"))
    )
    (net (code "21") (name "LED2TEMP") (class "Default")
      (node (ref "DRIVECONN") (pin "P$2") (pinfunction "P$2_P$2") (pintype "bidirectional"))
      (node (ref "TD-DM") (pin "P$11") (pinfunction "2B2_P$11") (pintype "bidirectional"))
    )
    (net (code "22") (name "LED3TEMP") (class "Default")
      (node (ref "DRIVECONN") (pin "P$3") (pinfunction "P$3_P$3") (pintype "bidirectional"))
      (node (ref "TD-DM") (pin "P$12") (pinfunction "2B3_P$12") (pintype "bidirectional"))
    )
    (net (code "23") (name "LED4TEMP") (class "Default")
      (node (ref "DRIVECONN") (pin "P$4") (pinfunction "P$4_P$4") (pintype "bidirectional"))
      (node (ref "TD-DM") (pin "P$13") (pinfunction "2B4_P$13") (pintype "bidirectional"))
    )
    (net (code "24") (name "LFE_1_MP_EN") (class "Default")
      (node (ref "BAL_1_BUF") (pin "P$4") (pinfunction "OUT_P$4") (pintype "bidirectional"))
      (node (ref "BATTCONN") (pin "P$9") (pinfunction "P$9_P$9") (pintype "bidirectional"))
    )
    (net (code "25") (name "LFE_1_MP_NCH") (class "Default")
      (node (ref "BATTCONN") (pin "P$10") (pinfunction "P$10_P$10") (pintype "bidirectional"))
      (node (ref "CH1-DM") (pin "P$2") (pinfunction "B3_P$2") (pintype "bidirectional"))
    )
    (net (code "26") (name "LFE_1_MP_NFLT") (class "Default")
      (node (ref "BATTCONN") (pin "P$11") (pinfunction "P$11_P$11") (pintype "bidirectional"))
      (node (ref "CH1-DM") (pin "P$1") (pinfunction "B4_P$1") (pintype "bidirectional"))
    )
    (net (code "27") (name "LFE_1_SENSE") (class "Default")
      (node (ref "BATTCONN") (pin "P$26") (pinfunction "P$26_P$26") (pintype "bidirectional"))
      (node (ref "CH1-DM") (pin "P$13") (pinfunction "B7_P$13") (pintype "bidirectional"))
    )
    (net (code "28") (name "LFE_1_V") (class "Default")
      (node (ref "BATTCONN") (pin "P$15") (pinfunction "P$15_P$15") (pintype "bidirectional"))
      (node (ref "CH2-DM") (pin "P$4") (pinfunction "B1_P$4") (pintype "bidirectional"))
    )
    (net (code "29") (name "LFE_2_MP_EN") (class "Default")
      (node (ref "BAL_2_BUF") (pin "P$4") (pinfunction "OUT_P$4") (pintype "bidirectional"))
      (node (ref "BATTCONN") (pin "P$12") (pinfunction "P$12_P$12") (pintype "bidirectional"))
    )
    (net (code "30") (name "LFE_2_MP_NCH") (class "Default")
      (node (ref "BATTCONN") (pin "P$13") (pinfunction "P$13_P$13") (pintype "bidirectional"))
      (node (ref "CH1-DM") (pin "P$15") (pinfunction "B5_P$15") (pintype "bidirectional"))
    )
    (net (code "31") (name "LFE_2_MP_NFLT") (class "Default")
      (node (ref "BATTCONN") (pin "P$14") (pinfunction "P$14_P$14") (pintype "bidirectional"))
      (node (ref "CH1-DM") (pin "P$14") (pinfunction "B6_P$14") (pintype "bidirectional"))
    )
    (net (code "32") (name "LFE_2_SENSE") (class "Default")
      (node (ref "BATTCONN") (pin "P$27") (pinfunction "P$27_P$27") (pintype "bidirectional"))
      (node (ref "CH1-DM") (pin "P$12") (pinfunction "B8_P$12") (pintype "bidirectional"))
    )
    (net (code "33") (name "LFE_2_V") (class "Default")
      (node (ref "BATTCONN") (pin "P$16") (pinfunction "P$16_P$16") (pintype "bidirectional"))
      (node (ref "CH2-DM") (pin "P$3") (pinfunction "B2_P$3") (pintype "bidirectional"))
    )
    (net (code "34") (name "LFE_3_V") (class "Default")
      (node (ref "BATTCONN") (pin "P$17") (pinfunction "P$17_P$17") (pintype "bidirectional"))
      (node (ref "CH2-DM") (pin "P$2") (pinfunction "B3_P$2") (pintype "bidirectional"))
    )
    (net (code "35") (name "LFE_4_V") (class "Default")
      (node (ref "BATTCONN") (pin "P$18") (pinfunction "P$18_P$18") (pintype "bidirectional"))
      (node (ref "CH2-DM") (pin "P$1") (pinfunction "B4_P$1") (pintype "bidirectional"))
    )
    (net (code "36") (name "LITH_MP_NCH") (class "Default")
      (node (ref "BATTCONN") (pin "P$7") (pinfunction "P$7_P$7") (pintype "bidirectional"))
      (node (ref "CH1-DM") (pin "P$4") (pinfunction "B1_P$4") (pintype "bidirectional"))
    )
    (net (code "37") (name "LITH_MP_NFLT") (class "Default")
      (node (ref "BATTCONN") (pin "P$8") (pinfunction "P$8_P$8") (pintype "bidirectional"))
      (node (ref "CH1-DM") (pin "P$3") (pinfunction "B2_P$3") (pintype "bidirectional"))
    )
    (net (code "38") (name "Net-(1N4148-PadCATHODE)") (class "Default")
      (node (ref "1N4148") (pin "CATHODE") (pinfunction "CATHODE_CATHODE") (pintype "bidirectional"))
      (node (ref "PH_AMP_1") (pin "OUT") (pinfunction "OUT_OUT") (pintype "output"))
      (node (ref "R32") (pin "1") (pinfunction "1_1") (pintype "passive"))
    )
    (net (code "39") (name "Net-(100T-1)") (class "Default")
      (node (ref "100T") (pin "P$1") (pinfunction "1_P$1") (pintype "bidirectional"))
      (node (ref "R16") (pin "2") (pinfunction "2_2") (pintype "passive"))
    )
    (net (code "40") (name "Net-(63001-L1)") (class "Default")
      (node (ref "63001") (pin "P$4") (pinfunction "L1_P$4") (pintype "input"))
      (node (ref "L2") (pin "1") (pinfunction "1_1") (pintype "passive"))
    )
    (net (code "41") (name "Net-(63001-L2)") (class "Default")
      (node (ref "63001") (pin "P$2") (pinfunction "L2_P$2") (pintype "input"))
      (node (ref "L2") (pin "2") (pinfunction "2_2") (pintype "passive"))
    )
    (net (code "42") (name "Net-(63002-L1)") (class "Default")
      (node (ref "63002") (pin "P$4") (pinfunction "L1_P$4") (pintype "input"))
      (node (ref "L3") (pin "1") (pinfunction "1_1") (pintype "passive"))
    )
    (net (code "43") (name "Net-(63002-L2)") (class "Default")
      (node (ref "63002") (pin "P$2") (pinfunction "L2_P$2") (pintype "input"))
      (node (ref "L3") (pin "2") (pinfunction "2_2") (pintype "passive"))
    )
    (net (code "44") (name "Net-(C21-Pad2)") (class "Default")
      (node (ref "C21") (pin "2") (pinfunction "2_2") (pintype "passive"))
      (node (ref "L4") (pin "2") (pinfunction "2_2") (pintype "passive"))
      (node (ref "LTC3112") (pin "10") (pinfunction "SW2_10") (pintype "bidirectional"))
      (node (ref "LTC3112") (pin "9") (pinfunction "SW2_9") (pintype "bidirectional"))
    )
    (net (code "45") (name "Net-(C22-Pad2)") (class "Default")
      (node (ref "C22") (pin "2") (pinfunction "2_2") (pintype "passive"))
      (node (ref "L4") (pin "1") (pinfunction "1_1") (pintype "passive"))
      (node (ref "LTC3112") (pin "12") (pinfunction "SW1_12") (pintype "bidirectional"))
      (node (ref "LTC3112") (pin "13") (pinfunction "SW1_13") (pintype "bidirectional"))
    )
    (net (code "46") (name "Net-(C29-Pad1)") (class "Default")
      (node (ref "C29") (pin "1") (pinfunction "1_1") (pintype "passive"))
      (node (ref "R10") (pin "1") (pinfunction "1_1") (pintype "passive"))
    )
    (net (code "47") (name "Net-(IR_PMOS-G)") (class "Default")
      (node (ref "IR_NMOS") (pin "P$5") (pinfunction "D_P$5") (pintype "passive"))
      (node (ref "IR_NMOS") (pin "P$6") (pinfunction "D_P$6") (pintype "passive"))
      (node (ref "IR_NMOS") (pin "P$7") (pinfunction "D_P$7") (pintype "passive"))
      (node (ref "IR_NMOS") (pin "P$8") (pinfunction "D_P$8") (pintype "passive"))
      (node (ref "IR_NMOS") (pin "P$9") (pinfunction "D_P$9") (pintype "passive"))
      (node (ref "IR_PMOS") (pin "4") (pinfunction "G_4") (pintype "passive"))
      (node (ref "R30") (pin "1") (pinfunction "1_1") (pintype "passive"))
    )
    (net (code "48") (name "Net-(LTC3112-BST1)") (class "Default")
      (node (ref "C22") (pin "1") (pinfunction "1_1") (pintype "passive"))
      (node (ref "LTC3112") (pin "14") (pinfunction "BST1_14") (pintype "bidirectional"))
    )
    (net (code "49") (name "Net-(LTC3112-BST2)") (class "Default")
      (node (ref "C21") (pin "1") (pinfunction "1_1") (pintype "passive"))
      (node (ref "LTC3112") (pin "11") (pinfunction "BST2_11") (pintype "bidirectional"))
    )
    (net (code "50") (name "Net-(LTC3112-COMP)") (class "Default")
      (node (ref "C28") (pin "1") (pinfunction "1_1") (pintype "passive"))
      (node (ref "C29") (pin "2") (pinfunction "2_2") (pintype "passive"))
      (node (ref "LTC3112") (pin "1") (pinfunction "COMP_1") (pintype "bidirectional"))
    )
    (net (code "51") (name "Net-(LTC3112-FB)") (class "Default")
      (node (ref "C28") (pin "2") (pinfunction "2_2") (pintype "passive"))
      (node (ref "LTC3112") (pin "2") (pinfunction "FB_2") (pintype "bidirectional"))
      (node (ref "R10") (pin "2") (pinfunction "2_2") (pintype "passive"))
      (node (ref "R3") (pin "2") (pinfunction "2_2") (pintype "passive"))
      (node (ref "R4") (pin "1") (pinfunction "1_1") (pintype "passive"))
    )
    (net (code "52") (name "Net-(LTC3112-OVP)") (class "Default")
      (node (ref "C26") (pin "1") (pinfunction "1_1") (pintype "passive"))
      (node (ref "LTC3112") (pin "3") (pinfunction "OVP_3") (pintype "bidirectional"))
      (node (ref "R6") (pin "2") (pinfunction "2_2") (pintype "passive"))
      (node (ref "R7") (pin "2") (pinfunction "2_2") (pintype "passive"))
    )
    (net (code "53") (name "Net-(LTC3112-VCC)") (class "Default")
      (node (ref "C23") (pin "2") (pinfunction "2_2") (pintype "passive"))
      (node (ref "LTC3112") (pin "15") (pinfunction "VCC_15") (pintype "bidirectional"))
    )
    (net (code "54") (name "Net-(MAG-C1)") (class "Default")
      (node (ref "C1") (pin "1") (pinfunction "1_1") (pintype "passive"))
      (node (ref "MAG") (pin "10") (pinfunction "C1_10") (pintype "bidirectional"))
    )
    (net (code "55") (name "Net-(MAG-SETP)") (class "Default")
      (node (ref "C10") (pin "1") (pinfunction "1_1") (pintype "passive"))
      (node (ref "MAG") (pin "8") (pinfunction "SETP_8") (pintype "bidirectional"))
    )
    (net (code "56") (name "Net-(MRAM-SO)") (class "Default")
      (node (ref "MRAM") (pin "P2") (pinfunction "SO_P2") (pintype "bidirectional"))
      (node (ref "SAMD21J") (pin "P$42") (pinfunction "PA21_P$42") (pintype "bidirectional"))
    )
    (net (code "57") (name "Net-(MRAM-~{CS})") (class "Default")
      (node (ref "MRAM") (pin "P1") (pinfunction "~{CS}_P1") (pintype "bidirectional"))
      (node (ref "R23") (pin "2") (pinfunction "2_2") (pintype "passive"))
      (node (ref "SAMD21J") (pin "P$41") (pinfunction "PA20_P$41") (pintype "bidirectional"))
    )
    (net (code "58") (name "Net-(PH_AMP_2-PadIN+)") (class "Default")
      (node (ref "PH_AMP_2") (pin "IN+") (pinfunction "IN+_IN+") (pintype "input"))
      (node (ref "R32") (pin "2") (pinfunction "2_2") (pintype "passive"))
      (node (ref "R33") (pin "2") (pinfunction "2_2") (pintype "passive"))
    )
    (net (code "59") (name "Net-(PH_AMP_2-PadIN-)") (class "Default")
      (node (ref "PH_AMP_2") (pin "IN-") (pinfunction "IN-_IN-") (pintype "input"))
      (node (ref "R34") (pin "1") (pinfunction "1_1") (pintype "passive"))
      (node (ref "R35") (pin "2") (pinfunction "2_2") (pintype "passive"))
    )
    (net (code "60") (name "Net-(R4-Pad2)") (class "Default")
      (node (ref "R4") (pin "2") (pinfunction "2_2") (pintype "passive"))
      (node (ref "R9") (pin "1") (pinfunction "1_1") (pintype "passive"))
    )
    (net (code "61") (name "Net-(R12-Pad1)") (class "Default")
      (node (ref "R12") (pin "1") (pinfunction "1_1") (pintype "passive"))
      (node (ref "R13") (pin "2") (pinfunction "2_2") (pintype "passive"))
      (node (ref "T_AMP") (pin "IN-") (pinfunction "IN-_IN-") (pintype "input"))
    )
    (net (code "62") (name "Net-(R13-Pad1)") (class "Default")
      (node (ref "R13") (pin "1") (pinfunction "1_1") (pintype "passive"))
      (node (ref "R14") (pin "2") (pinfunction "2_2") (pintype "passive"))
      (node (ref "T_AMP") (pin "OUT") (pinfunction "OUT_OUT") (pintype "output"))
    )
    (net (code "63") (name "Net-(R15-Pad1)") (class "Default")
      (node (ref "R15") (pin "1") (pinfunction "1_1") (pintype "passive"))
      (node (ref "R5") (pin "2") (pinfunction "2_2") (pintype "passive"))
      (node (ref "T_AMP") (pin "IN+") (pinfunction "IN+_IN+") (pintype "input"))
    )
    (net (code "64") (name "Net-(SAMD21J-VDDANA)") (class "Default")
      (node (ref "C2") (pin "2") (pinfunction "2_2") (pintype "passive"))
      (node (ref "C8") (pin "2") (pinfunction "2_2") (pintype "passive"))
      (node (ref "L1") (pin "2") (pinfunction "2_2") (pintype "passive"))
      (node (ref "SAMD21J") (pin "P$8") (pinfunction "VDDANA_P$8") (pintype "power_in"))
    )
    (net (code "65") (name "Net-(SAMD21J-VDDCORE)") (class "Default")
      (node (ref "C4") (pin "2") (pinfunction "2_2") (pintype "passive"))
      (node (ref "SAMD21J") (pin "P$55") (pinfunction "VDDCORE_P$55") (pintype "power_in"))
    )
    (net (code "66") (name "P29") (class "Default")
      (node (ref "RADCONNM") (pin "P$5") (pinfunction "5_P$5") (pintype "bidirectional"))
      (node (ref "RAD_SHDN_BUF") (pin "P$4") (pinfunction "OUT_P$4") (pintype "bidirectional"))
      (node (ref "UMBCONN") (pin "P$13") (pinfunction "P$13_P$13") (pintype "bidirectional"))
    )
    (net (code "67") (name "PA00") (class "Default")
      (node (ref "MAG") (pin "15") (pinfunction "DRDY_15") (pintype "bidirectional"))
      (node (ref "SAMD21J") (pin "P$1") (pinfunction "PA00_P$1") (pintype "bidirectional"))
    )
    (net (code "68") (name "PA01") (class "Default")
      (node (ref "SAMD21J") (pin "P$2") (pinfunction "PA01_P$2") (pintype "bidirectional"))
    )
    (net (code "69") (name "PA02") (class "Default")
      (node (ref "SAMD21J") (pin "P$3") (pinfunction "PA02_P$3") (pintype "bidirectional"))
    )
    (net (code "70") (name "PA03") (class "Default")
      (node (ref "SAMD21J") (pin "P$4") (pinfunction "PA03_P$4") (pintype "bidirectional"))
    )
    (net (code "71") (name "PA04") (class "Default")
      (node (ref "SAMD21J") (pin "P$13") (pinfunction "PA04_P$13") (pintype "bidirectional"))
    )
    (net (code "72") (name "PA05") (class "Default")
      (node (ref "SAMD21J") (pin "P$14") (pinfunction "PA05_P$14") (pintype "bidirectional"))
    )
    (net (code "73") (name "PA06") (class "Default")
      (node (ref "SAMD21J") (pin "P$15") (pinfunction "PA06_P$15") (pintype "bidirectional"))
    )
    (net (code "74") (name "PA07") (class "Default")
      (node (ref "SAMD21J") (pin "P$16") (pinfunction "PA07_P$16") (pintype "bidirectional"))
    )
    (net (code "75") (name "PA08") (class "Default")
      (node (ref "BAL_1_BUF") (pin "P$2") (pinfunction "IN_P$2") (pintype "bidirectional"))
      (node (ref "SAMD21J") (pin "P$17") (pinfunction "PA08_P$17") (pintype "bidirectional"))
    )
    (net (code "76") (name "PA09") (class "Default")
      (node (ref "BAL_2_BUF") (pin "P$2") (pinfunction "IN_P$2") (pintype "bidirectional"))
      (node (ref "SAMD21J") (pin "P$18") (pinfunction "PA09_P$18") (pintype "bidirectional"))
    )
    (net (code "77") (name "PA10") (class "Default")
      (node (ref "R18") (pin "1") (pinfunction "1_1") (pintype "passive"))
      (node (ref "SAMD21J") (pin "P$19") (pinfunction "PA10_P$19") (pintype "bidirectional"))
      (node (ref "TD-DM") (pin "P$1") (pinfunction "~{1OE}_P$1") (pintype "bidirectional"))
    )
    (net (code "78") (name "PA11") (class "Default")
      (node (ref "R19") (pin "1") (pinfunction "1_1") (pintype "passive"))
      (node (ref "SAMD21J") (pin "P$20") (pinfunction "PA11_P$20") (pintype "bidirectional"))
      (node (ref "TD-DM") (pin "P$15") (pinfunction "~{2OE}_P$15") (pintype "bidirectional"))
    )
    (net (code "79") (name "PA13") (class "Default")
      (node (ref "DRIVECONN") (pin "P$12") (pinfunction "P$12_P$12") (pintype "bidirectional"))
      (node (ref "SAMD21J") (pin "P$30") (pinfunction "PA13_P$30") (pintype "bidirectional"))
    )
    (net (code "80") (name "PA14") (class "Default")
      (node (ref "DRIVECONN") (pin "P$13") (pinfunction "P$13_P$13") (pintype "bidirectional"))
      (node (ref "SAMD21J") (pin "P$31") (pinfunction "PA14_P$31") (pintype "bidirectional"))
    )
    (net (code "81") (name "PA15") (class "Default")
      (node (ref "DRIVECONN") (pin "P$14") (pinfunction "P$14_P$14") (pintype "bidirectional"))
      (node (ref "SAMD21J") (pin "P$32") (pinfunction "PA15_P$32") (pintype "bidirectional"))
    )
    (net (code "82") (name "PA16") (class "Default")
      (node (ref "LED_EN_BUF") (pin "P$2") (pinfunction "IN_P$2") (pintype "bidirectional"))
      (node (ref "SAMD21J") (pin "P$35") (pinfunction "PA16_P$35") (pintype "bidirectional"))
    )
    (net (code "83") (name "PA17") (class "Default")
      (node (ref "IR_NMOS") (pin "P$4") (pinfunction "G_P$4") (pintype "passive"))
      (node (ref "R40") (pin "2") (pinfunction "2_2") (pintype "passive"))
      (node (ref "SAMD21J") (pin "P$36") (pinfunction "PA17_P$36") (pintype "bidirectional"))
      (node (ref "UMBCONN") (pin "P$6") (pinfunction "P$6_P$6") (pintype "bidirectional"))
    )
    (net (code "84") (name "PA18") (class "Default")
      (node (ref "MRAM") (pin "P5") (pinfunction "SI_P5") (pintype "bidirectional"))
      (node (ref "R28") (pin "1") (pinfunction "1_1") (pintype "passive"))
      (node (ref "SAMD21J") (pin "P$37") (pinfunction "PA18_P$37") (pintype "bidirectional"))
    )
    (net (code "85") (name "PA19") (class "Default")
      (node (ref "MRAM") (pin "P6") (pinfunction "SCK_P6") (pintype "bidirectional"))
      (node (ref "R29") (pin "1") (pinfunction "1_1") (pintype "passive"))
      (node (ref "SAMD21J") (pin "P$38") (pinfunction "PA19_P$38") (pintype "bidirectional"))
    )
    (net (code "86") (name "PA22") (class "Default")
      (node (ref "DRIVECONN") (pin "P$15") (pinfunction "P$15_P$15") (pintype "bidirectional"))
      (node (ref "SAMD21J") (pin "P$43") (pinfunction "PA22_P$43") (pintype "bidirectional"))
    )
    (net (code "87") (name "PA23") (class "Default")
      (node (ref "DRIVECONN") (pin "P$16") (pinfunction "P$16_P$16") (pintype "bidirectional"))
      (node (ref "SAMD21J") (pin "P$44") (pinfunction "PA23_P$44") (pintype "bidirectional"))
    )
    (net (code "88") (name "PA24") (class "Default")
      (node (ref "SAMD21J") (pin "P$45") (pinfunction "PA24_P$45") (pintype "bidirectional"))
      (node (ref "TX_BUF") (pin "P$2") (pinfunction "IN_P$2") (pintype "bidirectional"))
    )
    (net (code "89") (name "PA25") (class "Default")
      (node (ref "RX_BUF") (pin "P$4") (pinfunction "OUT_P$4") (pintype "bidirectional"))
      (node (ref "SAMD21J") (pin "P$46") (pinfunction "PA25_P$46") (pintype "bidirectional"))
    )
    (net (code "90") (name "PA27") (class "Default")
      (node (ref "CH1-DM") (pin "P$7") (pinfunction "~{OE}_P$7") (pintype "bidirectional"))
      (node (ref "R22") (pin "1") (pinfunction "1_1") (pintype "passive"))
      (node (ref "SAMD21J") (pin "P$51") (pinfunction "PA27_P$51") (pintype "bidirectional"))
    )
    (net (code "91") (name "PA28") (class "Default")
      (node (ref "CH2-DM") (pin "P$7") (pinfunction "~{OE}_P$7") (pintype "bidirectional"))
      (node (ref "R31") (pin "1") (pinfunction "1_1") (pintype "passive"))
      (node (ref "SAMD21J") (pin "P$53") (pinfunction "PA28_P$53") (pintype "bidirectional"))
    )
    (net (code "92") (name "PA30") (class "Default")
      (node (ref "PROGCONN") (pin "9") (pinfunction "9_9") (pintype "bidirectional"))
      (node (ref "SAMD21J") (pin "P$57") (pinfunction "PA30_P$57") (pintype "bidirectional"))
      (node (ref "UMBCONN") (pin "P$2") (pinfunction "P$2_P$2") (pintype "bidirectional"))
    )
    (net (code "93") (name "PA31") (class "Default")
      (node (ref "PROGCONN") (pin "10") (pinfunction "10_10") (pintype "bidirectional"))
      (node (ref "SAMD21J") (pin "P$58") (pinfunction "PA31_P$58") (pintype "bidirectional"))
      (node (ref "UMBCONN") (pin "P$3") (pinfunction "P$3_P$3") (pintype "bidirectional"))
    )
    (net (code "94") (name "PB00") (class "Default")
      (node (ref "C17") (pin "1") (pinfunction "1_1") (pintype "passive"))
      (node (ref "CH1-DM") (pin "P$5") (pinfunction "A_P$5") (pintype "bidirectional"))
      (node (ref "CH2-DM") (pin "P$5") (pinfunction "A_P$5") (pintype "bidirectional"))
      (node (ref "PH_AMP_2") (pin "OUT") (pinfunction "OUT_OUT") (pintype "output"))
      (node (ref "R14") (pin "1") (pinfunction "1_1") (pintype "passive"))
      (node (ref "R34") (pin "2") (pinfunction "2_2") (pintype "passive"))
      (node (ref "SAMD21J") (pin "P$61") (pinfunction "PB00_P$61") (pintype "bidirectional"))
      (node (ref "TD-DM") (pin "P$7") (pinfunction "1A_P$7") (pintype "bidirectional"))
    )
    (net (code "95") (name "PB01") (class "Default")
      (node (ref "RAD_SHDN_BUF") (pin "P$2") (pinfunction "IN_P$2") (pintype "bidirectional"))
      (node (ref "SAMD21J") (pin "P$62") (pinfunction "PB01_P$62") (pintype "bidirectional"))
    )
    (net (code "96") (name "PB02") (class "Default")
      (node (ref "R11") (pin "1") (pinfunction "1_1") (pintype "passive"))
      (node (ref "SAMD21J") (pin "P$63") (pinfunction "PB02_P$63") (pintype "bidirectional"))
      (node (ref "TX_BUF") (pin "P$1") (pinfunction "~{OE}_P$1") (pintype "bidirectional"))
    )
    (net (code "97") (name "PB03") (class "Default")
      (node (ref "R38") (pin "2") (pinfunction "2_2") (pintype "passive"))
      (node (ref "RX_BUF") (pin "P$1") (pinfunction "~{OE}_P$1") (pintype "bidirectional"))
      (node (ref "SAMD21J") (pin "P$64") (pinfunction "PB03_P$64") (pintype "bidirectional"))
    )
    (net (code "98") (name "PB04") (class "Default")
      (node (ref "SAMD21J") (pin "P$5") (pinfunction "PB04_P$5") (pintype "bidirectional"))
    )
    (net (code "99") (name "PB05") (class "Default")
      (node (ref "SAMD21J") (pin "P$6") (pinfunction "PB05_P$6") (pintype "bidirectional"))
    )
    (net (code "100") (name "PB06") (class "Default")
      (node (ref "C27") (pin "1") (pinfunction "1_1") (pintype "passive"))
      (node (ref "LTC3112") (pin "7") (pinfunction "IOUT_7") (pintype "bidirectional"))
      (node (ref "R8") (pin "2") (pinfunction "2_2") (pintype "passive"))
      (node (ref "SAMD21J") (pin "P$9") (pinfunction "PB06_P$9") (pintype "bidirectional"))
    )
    (net (code "101") (name "PB07") (class "Default")
      (node (ref "SAMD21J") (pin "P$10") (pinfunction "PB07_P$10") (pintype "bidirectional"))
    )
    (net (code "102") (name "PB08") (class "Default")
      (node (ref "SAMD21J") (pin "P$11") (pinfunction "PB08_P$11") (pintype "bidirectional"))
    )
    (net (code "103") (name "PB09") (class "Default")
      (node (ref "SAMD21J") (pin "P$12") (pinfunction "PB09_P$12") (pintype "bidirectional"))
    )
    (net (code "104") (name "PB10") (class "Default")
      (node (ref "CH1-DM") (pin "P$9") (pinfunction "S2_P$9") (pintype "bidirectional"))
      (node (ref "CH2-DM") (pin "P$9") (pinfunction "S2_P$9") (pintype "bidirectional"))
      (node (ref "PH-DM") (pin "P$9") (pinfunction "S2_P$9") (pintype "bidirectional"))
      (node (ref "SAMD21J") (pin "P$23") (pinfunction "PB10_P$23") (pintype "bidirectional"))
      (node (ref "T-DM") (pin "P$9") (pinfunction "S2_P$9") (pintype "bidirectional"))
    )
    (net (code "105") (name "PB11") (class "Default")
      (node (ref "BATTCONN") (pin "P$6") (pinfunction "P$6_P$6") (pintype "bidirectional"))
      (node (ref "SAMD21J") (pin "P$24") (pinfunction "PB11_P$24") (pintype "bidirectional"))
    )
    (net (code "106") (name "PB12") (class "Default")
      (node (ref "CONNSIDE1") (pin "P$3") (pinfunction "3_P$3") (pintype "passive"))
      (node (ref "CONNSIDE2") (pin "P$3") (pinfunction "3_P$3") (pintype "passive"))
      (node (ref "CONNSIDE3") (pin "P$3") (pinfunction "3_P$3") (pintype "passive"))
      (node (ref "CONNSIDE4") (pin "P$3") (pinfunction "3_P$3") (pintype "passive"))
      (node (ref "CONNSIDE5") (pin "P$3") (pinfunction "3_P$3") (pintype "passive"))
      (node (ref "DRIVECONN") (pin "P$10") (pinfunction "P$10_P$10") (pintype "bidirectional"))
      (node (ref "MAG") (pin "16") (pinfunction "SDA_16") (pintype "bidirectional"))
      (node (ref "R2") (pin "2") (pinfunction "2_2") (pintype "passive"))
      (node (ref "R25") (pin "1") (pinfunction "1_1") (pintype "passive"))
      (node (ref "SAMD21J") (pin "P$25") (pinfunction "PB12_P$25") (pintype "bidirectional"))
    )
    (net (code "107") (name "PB13") (class "Default")
      (node (ref "CONNSIDE1") (pin "P$2") (pinfunction "2_P$2") (pintype "passive"))
      (node (ref "CONNSIDE2") (pin "P$2") (pinfunction "2_P$2") (pintype "passive"))
      (node (ref "CONNSIDE3") (pin "P$2") (pinfunction "2_P$2") (pintype "passive"))
      (node (ref "CONNSIDE4") (pin "P$2") (pinfunction "2_P$2") (pintype "passive"))
      (node (ref "CONNSIDE5") (pin "P$2") (pinfunction "2_P$2") (pintype "passive"))
      (node (ref "DRIVECONN") (pin "P$9") (pinfunction "P$9_P$9") (pintype "bidirectional"))
      (node (ref "MAG") (pin "1") (pinfunction "SCL_1") (pintype "bidirectional"))
      (node (ref "R1") (pin "2") (pinfunction "2_2") (pintype "passive"))
      (node (ref "R24") (pin "1") (pinfunction "1_1") (pintype "passive"))
      (node (ref "SAMD21J") (pin "P$26") (pinfunction "PB13_P$26") (pintype "bidirectional"))
    )
    (net (code "108") (name "PB15") (class "Default")
      (node (ref "SAMD21J") (pin "P$28") (pinfunction "PB15_P$28") (pintype "bidirectional"))
    )
    (net (code "109") (name "PB16") (class "Default")
      (node (ref "MRAM") (pin "P3") (pinfunction "~{WP}_P3") (pintype "bidirectional"))
      (node (ref "R26") (pin "1") (pinfunction "1_1") (pintype "passive"))
      (node (ref "SAMD21J") (pin "P$39") (pinfunction "PB16_P$39") (pintype "bidirectional"))
    )
    (net (code "110") (name "PB17") (class "Default")
      (node (ref "MRAM") (pin "P7") (pinfunction "~{HOLD}_P7") (pintype "bidirectional"))
      (node (ref "R27") (pin "1") (pinfunction "1_1") (pintype "passive"))
      (node (ref "SAMD21J") (pin "P$40") (pinfunction "PB17_P$40") (pintype "bidirectional"))
    )
    (net (code "111") (name "PB22") (class "Default")
      (node (ref "CH1-DM") (pin "P$11") (pinfunction "S0_P$11") (pintype "bidirectional"))
      (node (ref "CH2-DM") (pin "P$11") (pinfunction "S0_P$11") (pintype "bidirectional"))
      (node (ref "PH-DM") (pin "P$11") (pinfunction "S0_P$11") (pintype "bidirectional"))
      (node (ref "SAMD21J") (pin "P$49") (pinfunction "PB22_P$49") (pintype "bidirectional"))
      (node (ref "T-DM") (pin "P$11") (pinfunction "S0_P$11") (pintype "bidirectional"))
      (node (ref "TD-DM") (pin "P$14") (pinfunction "S0_P$14") (pintype "bidirectional"))
    )
    (net (code "112") (name "PB23") (class "Default")
      (node (ref "CH1-DM") (pin "P$10") (pinfunction "S1_P$10") (pintype "bidirectional"))
      (node (ref "CH2-DM") (pin "P$10") (pinfunction "S1_P$10") (pintype "bidirectional"))
      (node (ref "PH-DM") (pin "P$10") (pinfunction "S1_P$10") (pintype "bidirectional"))
      (node (ref "SAMD21J") (pin "P$50") (pinfunction "PB23_P$50") (pintype "bidirectional"))
      (node (ref "T-DM") (pin "P$10") (pinfunction "S1_P$10") (pintype "bidirectional"))
      (node (ref "TD-DM") (pin "P$2") (pinfunction "S1_P$2") (pintype "bidirectional"))
    )
    (net (code "113") (name "PB30") (class "Default")
      (node (ref "R20") (pin "1") (pinfunction "1_1") (pintype "passive"))
      (node (ref "SAMD21J") (pin "P$59") (pinfunction "PB30_P$59") (pintype "bidirectional"))
      (node (ref "T-DM") (pin "P$7") (pinfunction "~{OE}_P$7") (pintype "bidirectional"))
    )
    (net (code "114") (name "PB31") (class "Default")
      (node (ref "PH-DM") (pin "P$7") (pinfunction "~{OE}_P$7") (pintype "bidirectional"))
      (node (ref "R21") (pin "1") (pinfunction "1_1") (pintype "passive"))
      (node (ref "SAMD21J") (pin "P$60") (pinfunction "PB31_P$60") (pintype "bidirectional"))
    )
    (net (code "115") (name "PD1_OUT") (class "Default")
      (node (ref "CONNSIDE1") (pin "P$1") (pinfunction "1_P$1") (pintype "passive"))
      (node (ref "PH-DM") (pin "P$4") (pinfunction "B1_P$4") (pintype "bidirectional"))
    )
    (net (code "116") (name "PD2_OUT") (class "Default")
      (node (ref "CONNSIDE2") (pin "P$1") (pinfunction "1_P$1") (pintype "passive"))
      (node (ref "PH-DM") (pin "P$3") (pinfunction "B2_P$3") (pintype "bidirectional"))
    )
    (net (code "117") (name "PD3_OUT") (class "Default")
      (node (ref "CONNSIDE3") (pin "P$1") (pinfunction "1_P$1") (pintype "passive"))
      (node (ref "PH-DM") (pin "P$2") (pinfunction "B3_P$2") (pintype "bidirectional"))
    )
    (net (code "118") (name "PD4_OUT") (class "Default")
      (node (ref "CONNSIDE4") (pin "P$1") (pinfunction "1_P$1") (pintype "passive"))
      (node (ref "PH-DM") (pin "P$1") (pinfunction "B4_P$1") (pintype "bidirectional"))
    )
    (net (code "119") (name "PD5_OUT") (class "Default")
      (node (ref "CONNSIDE5") (pin "P$1") (pinfunction "1_P$1") (pintype "passive"))
      (node (ref "PH-DM") (pin "P$15") (pinfunction "B5_P$15") (pintype "bidirectional"))
    )
    (net (code "120") (name "PD_OUT") (class "Default")
      (node (ref "DRIVECONN") (pin "P$11") (pinfunction "P$11_P$11") (pintype "bidirectional"))
      (node (ref "PH-DM") (pin "P$14") (pinfunction "B6_P$14") (pintype "bidirectional"))
    )
    (net (code "121") (name "PH_IN") (class "Default")
      (node (ref "1N4148") (pin "ANODE") (pinfunction "ANODE_ANODE") (pintype "bidirectional"))
      (node (ref "PH-DM") (pin "P$5") (pinfunction "A_P$5") (pintype "bidirectional"))
      (node (ref "PH_AMP_1") (pin "IN-") (pinfunction "IN-_IN-") (pintype "input"))
    )
    (net (code "122") (name "R2") (class "Default")
      (node (ref "RADCONNM") (pin "P$6") (pinfunction "6_P$6") (pintype "bidirectional"))
      (node (ref "SEND") (pin "A") (pinfunction "A_A") (pintype "bidirectional"))
      (node (ref "UMBCONN") (pin "P$11") (pinfunction "P$11_P$11") (pintype "bidirectional"))
    )
    (net (code "123") (name "R3") (class "Default")
      (node (ref "RADCONNM") (pin "P$7") (pinfunction "7_P$7") (pintype "bidirectional"))
      (node (ref "TX_BUF") (pin "P$4") (pinfunction "OUT_P$4") (pintype "bidirectional"))
      (node (ref "UMBCONN") (pin "P$8") (pinfunction "P$8_P$8") (pintype "bidirectional"))
    )
    (net (code "124") (name "R4") (class "Default")
      (node (ref "RADCONNM") (pin "P$8") (pinfunction "8_P$8") (pintype "bidirectional"))
      (node (ref "RET") (pin "A") (pinfunction "A_A") (pintype "bidirectional"))
      (node (ref "UMBCONN") (pin "P$12") (pinfunction "P$12_P$12") (pintype "bidirectional"))
    )
    (net (code "125") (name "R12") (class "Default")
      (node (ref "PWR_ON") (pin "A") (pinfunction "A_A") (pintype "bidirectional"))
      (node (ref "RADCONNM") (pin "P$3") (pinfunction "3_P$3") (pintype "bidirectional"))
      (node (ref "UMBCONN") (pin "P$10") (pinfunction "P$10_P$10") (pintype "bidirectional"))
    )
    (net (code "126") (name "R14") (class "Default")
      (node (ref "RADCONNM") (pin "P$4") (pinfunction "4_P$4") (pintype "bidirectional"))
      (node (ref "RX_BUF") (pin "P$2") (pinfunction "IN_P$2") (pintype "bidirectional"))
      (node (ref "UMBCONN") (pin "P$9") (pinfunction "P$9_P$9") (pintype "bidirectional"))
    )
    (net (code "127") (name "RESETN") (class "Default")
      (node (ref "PROGCONN") (pin "6") (pinfunction "6_6") (pintype "bidirectional"))
      (node (ref "SAMD21J") (pin "P$52") (pinfunction "RESETN_P$52") (pintype "input"))
      (node (ref "UMBCONN") (pin "P$1") (pinfunction "P$1_P$1") (pintype "bidirectional"))
    )
    (net (code "128") (name "SCL") (class "Default")
      (node (ref "UMBCONN") (pin "P$5") (pinfunction "P$5_P$5") (pintype "bidirectional"))
    )
    (net (code "129") (name "SDA") (class "Default")
      (node (ref "UMBCONN") (pin "P$4") (pinfunction "P$4_P$4") (pintype "bidirectional"))
    )
    (net (code "130") (name "SETC") (class "Default")
      (node (ref "C10") (pin "2") (pinfunction "2_2") (pintype "passive"))
      (node (ref "MAG") (pin "12") (pinfunction "SETC_12") (pintype "bidirectional"))
    )
    (net (code "131") (name "SHDN_N") (class "Default")
      (node (ref "BATTCONN") (pin "P$19") (pinfunction "P$19_P$19") (pintype "bidirectional"))
      (node (ref "DRIVECONN") (pin "P$27") (pinfunction "P$27_P$27") (pintype "bidirectional"))
      (node (ref "LED_EN_BUF") (pin "P$4") (pinfunction "OUT_P$4") (pintype "bidirectional"))
      (node (ref "R37") (pin "2") (pinfunction "2_2") (pintype "passive"))
      (node (ref "UMBCONN") (pin "P$7") (pinfunction "P$7_P$7") (pintype "bidirectional"))
    )
    (net (code "132") (name "TEMP_IN") (class "Default")
      (node (ref "100T") (pin "P$3") (pinfunction "3_P$3") (pintype "bidirectional"))
      (node (ref "R15") (pin "2") (pinfunction "2_2") (pintype "passive"))
      (node (ref "T-DM") (pin "P$5") (pinfunction "A_P$5") (pintype "bidirectional"))
      (node (ref "TD-DM") (pin "P$9") (pinfunction "2A_P$9") (pintype "bidirectional"))
    )
    (net (code "133") (name "UMB_ENABLE") (class "Default")
      (node (ref "BAL_1_BUF") (pin "P$1") (pinfunction "~{OE}_P$1") (pintype "bidirectional"))
      (node (ref "BAL_2_BUF") (pin "P$1") (pinfunction "~{OE}_P$1") (pintype "bidirectional"))
      (node (ref "LED_EN_BUF") (pin "P$1") (pinfunction "~{OE}_P$1") (pintype "bidirectional"))
      (node (ref "R36") (pin "2") (pinfunction "2_2") (pintype "passive"))
      (node (ref "RAD_SHDN_BUF") (pin "P$1") (pinfunction "~{OE}_P$1") (pintype "bidirectional"))
      (node (ref "UMBCONN") (pin "P$14") (pinfunction "P$14_P$14") (pintype "bidirectional"))
    )
    (net (code "134") (name "VIN") (class "Default")
      (node (ref "63001") (pin "P$5") (pinfunction "VIN_P$5") (pintype "input"))
      (node (ref "63001") (pin "P$6") (pinfunction "EN_P$6") (pintype "input"))
      (node (ref "63001") (pin "P$7") (pinfunction "PS/SYNC_P$7") (pintype "input"))
      (node (ref "63001") (pin "P$8") (pinfunction "VINA_P$8") (pintype "input"))
      (node (ref "63002") (pin "P$5") (pinfunction "VIN_P$5") (pintype "input"))
      (node (ref "63002") (pin "P$6") (pinfunction "EN_P$6") (pintype "input"))
      (node (ref "63002") (pin "P$7") (pinfunction "PS/SYNC_P$7") (pintype "input"))
      (node (ref "63002") (pin "P$8") (pinfunction "VINA_P$8") (pintype "input"))
      (node (ref "BATTCONN") (pin "P$23") (pinfunction "P$23_P$23") (pintype "bidirectional"))
      (node (ref "BATTCONN") (pin "P$24") (pinfunction "P$24_P$24") (pintype "bidirectional"))
      (node (ref "BATTCONN") (pin "P$25") (pinfunction "P$25_P$25") (pintype "bidirectional"))
      (node (ref "C12") (pin "1") (pinfunction "1_1") (pintype "passive"))
      (node (ref "C14") (pin "2") (pinfunction "2_2") (pintype "passive"))
      (node (ref "C19") (pin "1") (pinfunction "1_1") (pintype "passive"))
      (node (ref "CH2-DM") (pin "P$15") (pinfunction "B5_P$15") (pintype "bidirectional"))
      (node (ref "LTC3112") (pin "16") (pinfunction "PWM/SYNC_16") (pintype "bidirectional"))
      (node (ref "LTC3112") (pin "4") (pinfunction "VIN_4") (pintype "bidirectional"))
      (node (ref "LTC3112") (pin "5") (pinfunction "VIN_5") (pintype "bidirectional"))
      (node (ref "LTC3112") (pin "6") (pinfunction "RUN_6") (pintype "bidirectional"))
    )
    (net (code "135") (name "unconnected-(100T-2-PadP$2)") (class "Default")
      (node (ref "100T") (pin "P$2") (pinfunction "2_P$2") (pintype "bidirectional"))
    )
    (net (code "136") (name "unconnected-(CH1-DM-NC-PadP$6)") (class "Default")
      (node (ref "CH1-DM") (pin "P$6") (pinfunction "NC_P$6") (pintype "bidirectional"))
    )
    (net (code "137") (name "unconnected-(CH2-DM-B6-PadP$14)") (class "Default")
      (node (ref "CH2-DM") (pin "P$14") (pinfunction "B6_P$14") (pintype "bidirectional"))
    )
    (net (code "138") (name "unconnected-(CH2-DM-B7-PadP$13)") (class "Default")
      (node (ref "CH2-DM") (pin "P$13") (pinfunction "B7_P$13") (pintype "bidirectional"))
    )
    (net (code "139") (name "unconnected-(CH2-DM-B8-PadP$12)") (class "Default")
      (node (ref "CH2-DM") (pin "P$12") (pinfunction "B8_P$12") (pintype "bidirectional"))
    )
    (net (code "140") (name "unconnected-(CH2-DM-NC-PadP$6)") (class "Default")
      (node (ref "CH2-DM") (pin "P$6") (pinfunction "NC_P$6") (pintype "bidirectional"))
    )
    (net (code "141") (name "unconnected-(CONNSIDE1-6-PadP$6)") (class "Default")
      (node (ref "CONNSIDE1") (pin "P$6") (pinfunction "6_P$6") (pintype "passive"))
    )
    (net (code "142") (name "unconnected-(CONNSIDE2-6-PadP$6)") (class "Default")
      (node (ref "CONNSIDE2") (pin "P$6") (pinfunction "6_P$6") (pintype "passive"))
    )
    (net (code "143") (name "unconnected-(CONNSIDE3-6-PadP$6)") (class "Default")
      (node (ref "CONNSIDE3") (pin "P$6") (pinfunction "6_P$6") (pintype "passive"))
    )
    (net (code "144") (name "unconnected-(CONNSIDE4-6-PadP$6)") (class "Default")
      (node (ref "CONNSIDE4") (pin "P$6") (pinfunction "6_P$6") (pintype "passive"))
    )
    (net (code "145") (name "unconnected-(CONNSIDE5-6-PadP$6)") (class "Default")
      (node (ref "CONNSIDE5") (pin "P$6") (pinfunction "6_P$6") (pintype "passive"))
    )
    (net (code "146") (name "unconnected-(DRIVECONN-PadP$21)") (class "Default")
      (node (ref "DRIVECONN") (pin "P$21") (pinfunction "P$21_P$21") (pintype "bidirectional"))
    )
    (net (code "147") (name "unconnected-(DRIVECONN-PadP$22)") (class "Default")
      (node (ref "DRIVECONN") (pin "P$22") (pinfunction "P$22_P$22") (pintype "bidirectional"))
    )
    (net (code "148") (name "unconnected-(DRIVECONN-PadP$23)") (class "Default")
      (node (ref "DRIVECONN") (pin "P$23") (pinfunction "P$23_P$23") (pintype "bidirectional"))
    )
    (net (code "149") (name "unconnected-(MAG-NC-Pad3)") (class "Default")
      (node (ref "MAG") (pin "3") (pinfunction "NC_3") (pintype "bidirectional"))
    )
    (net (code "150") (name "unconnected-(MAG-NC-Pad5)") (class "Default")
      (node (ref "MAG") (pin "5") (pinfunction "NC_5") (pintype "bidirectional"))
    )
    (net (code "151") (name "unconnected-(MAG-NC-Pad6)") (class "Default")
      (node (ref "MAG") (pin "6") (pinfunction "NC_6") (pintype "bidirectional"))
    )
    (net (code "152") (name "unconnected-(MAG-NC-Pad7)") (class "Default")
      (node (ref "MAG") (pin "7") (pinfunction "NC_7") (pintype "bidirectional"))
    )
    (net (code "153") (name "unconnected-(MAG-NC-Pad14)") (class "Default")
      (node (ref "MAG") (pin "14") (pinfunction "NC_14") (pintype "bidirectional"))
    )
    (net (code "154") (name "unconnected-(PH-DM-B7-PadP$13)") (class "Default")
      (node (ref "PH-DM") (pin "P$13") (pinfunction "B7_P$13") (pintype "bidirectional"))
    )
    (net (code "155") (name "unconnected-(PH-DM-B8-PadP$12)") (class "Default")
      (node (ref "PH-DM") (pin "P$12") (pinfunction "B8_P$12") (pintype "bidirectional"))
    )
    (net (code "156") (name "unconnected-(PH-DM-NC-PadP$6)") (class "Default")
      (node (ref "PH-DM") (pin "P$6") (pinfunction "NC_P$6") (pintype "bidirectional"))
    )
    (net (code "157") (name "unconnected-(PROGCONN-Pad4)") (class "Default")
      (node (ref "PROGCONN") (pin "4") (pinfunction "4_4") (pintype "bidirectional"))
    )
    (net (code "158") (name "unconnected-(PROGCONN-Pad5)") (class "Default")
      (node (ref "PROGCONN") (pin "5") (pinfunction "5_5") (pintype "bidirectional"))
    )
    (net (code "159") (name "unconnected-(PROGCONN-Pad7)") (class "Default")
      (node (ref "PROGCONN") (pin "7") (pinfunction "7_7") (pintype "bidirectional"))
    )
    (net (code "160") (name "unconnected-(PROGCONN-Pad8)") (class "Default")
      (node (ref "PROGCONN") (pin "8") (pinfunction "8_8") (pintype "bidirectional"))
    )
    (net (code "161") (name "unconnected-(SAMD21J-PA12-PadP$29)") (class "Default")
      (node (ref "SAMD21J") (pin "P$29") (pinfunction "PA12_P$29") (pintype "bidirectional"))
    )
    (net (code "162") (name "unconnected-(SAMD21J-PB14-PadP$27)") (class "Default")
      (node (ref "SAMD21J") (pin "P$27") (pinfunction "PB14_P$27") (pintype "bidirectional"))
    )
    (net (code "163") (name "unconnected-(T-DM-NC-PadP$6)") (class "Default")
      (node (ref "T-DM") (pin "P$6") (pinfunction "NC_P$6") (pintype "bidirectional"))
    )
  )
)
